# core_io1.net
KiCad netlist of a schematic drawn in EAGLE
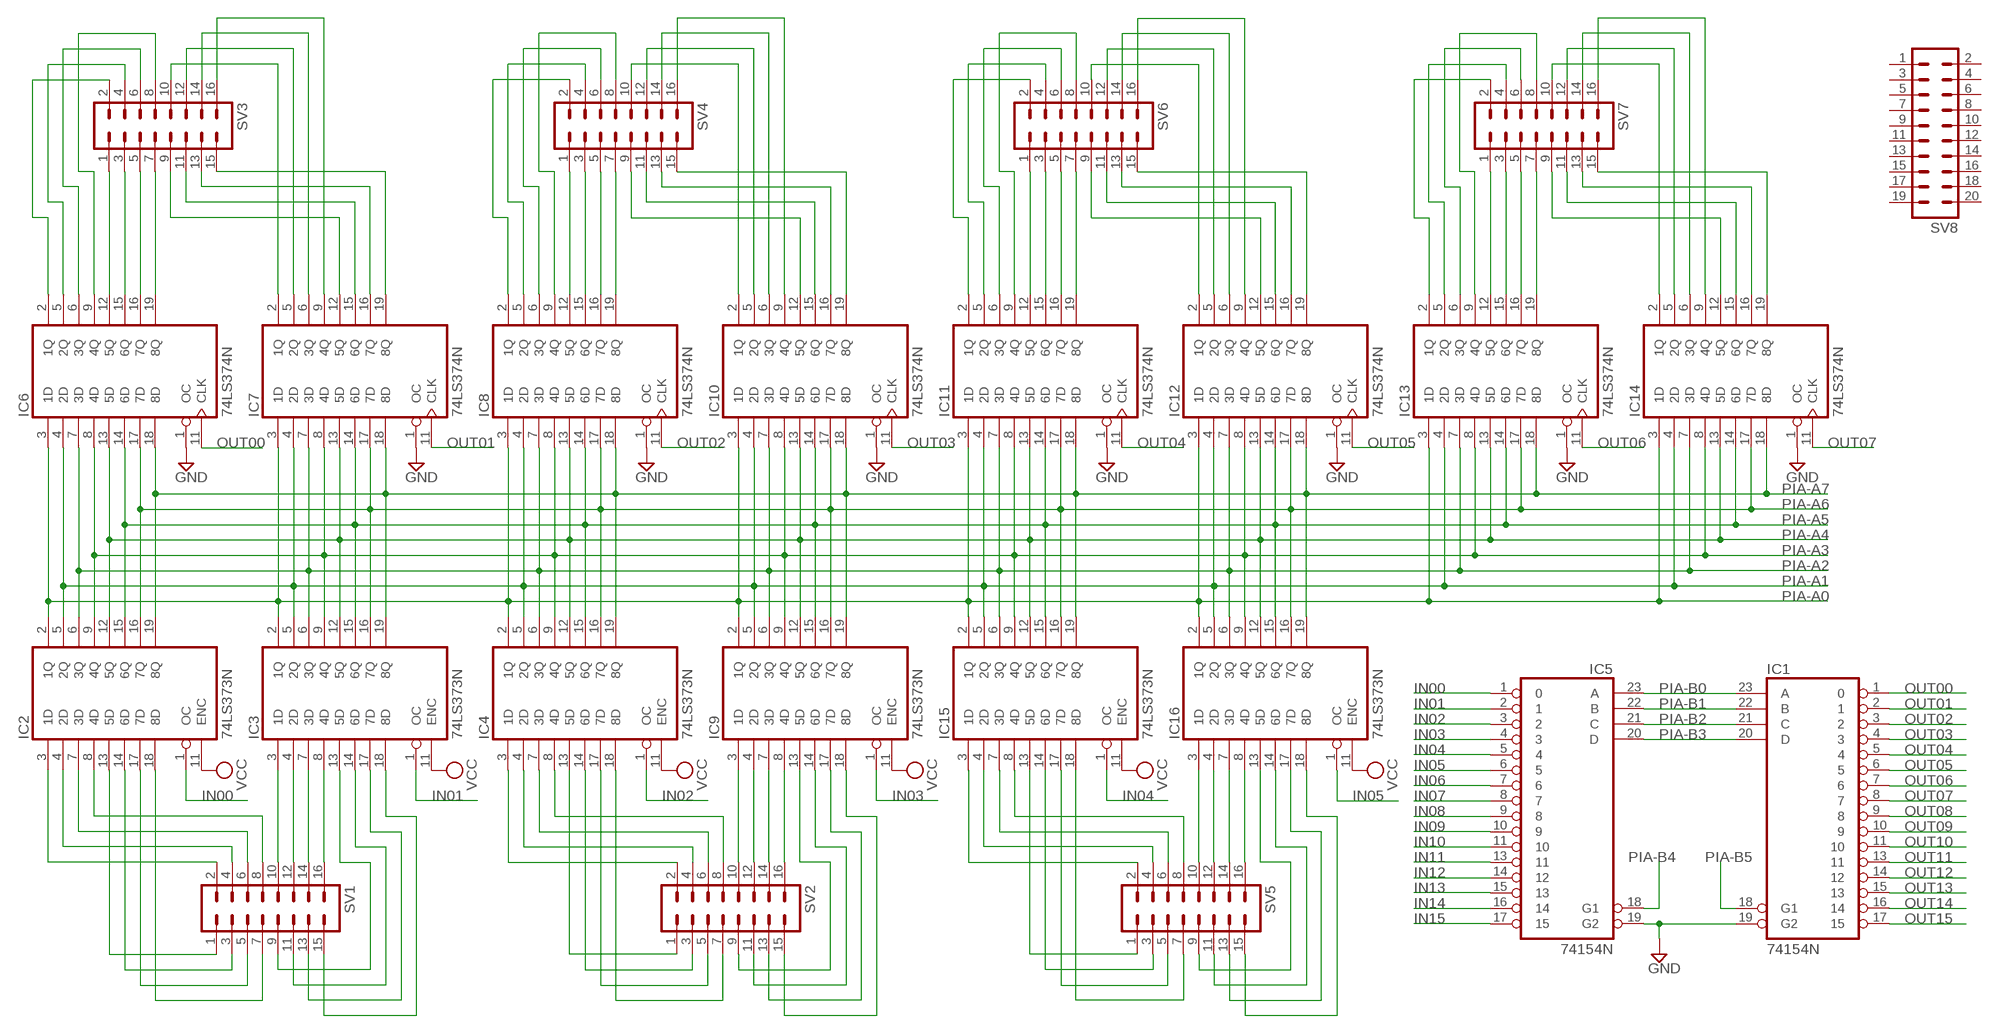
[diagram p0: schematic, sheet 1]
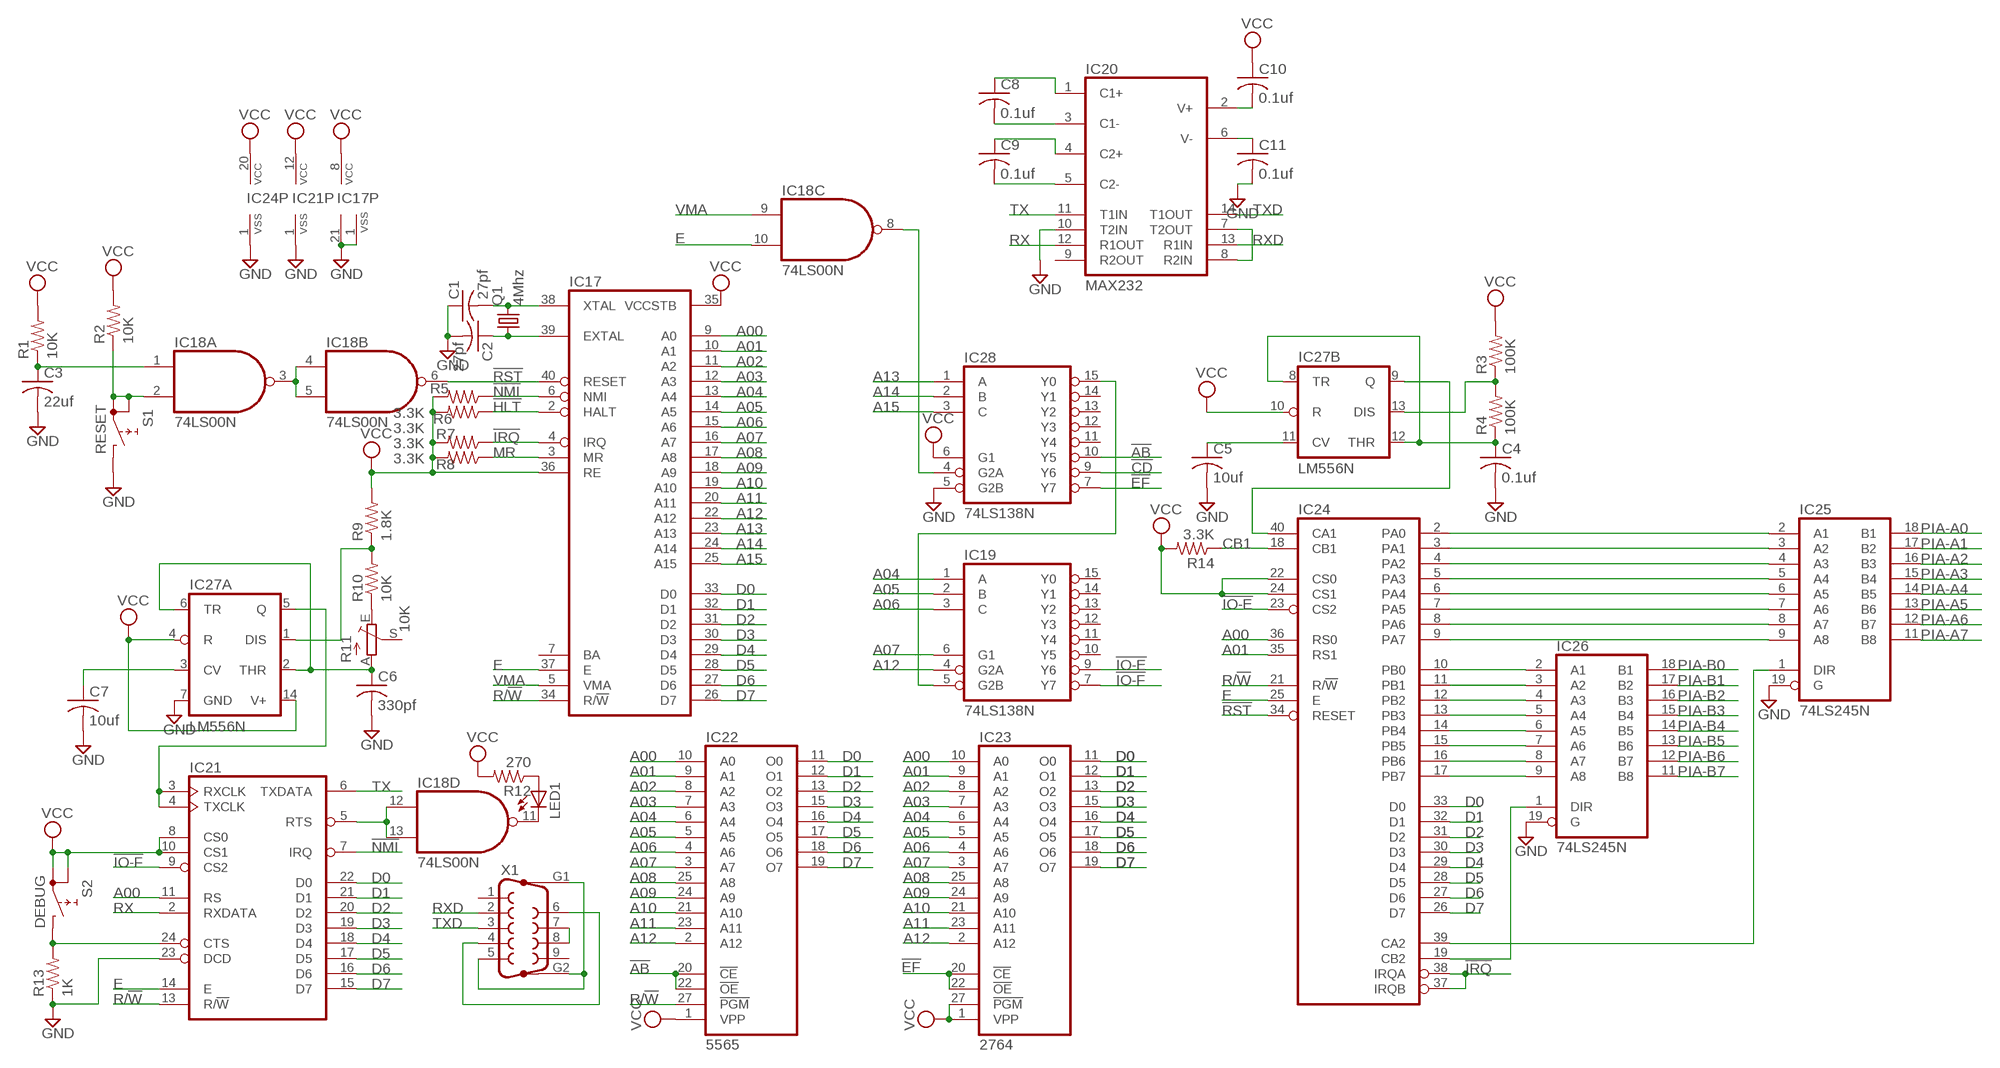
[diagram p1: schematic, sheet 2]

(export (version "E")
  (design (tool "Eeschema 10.0.6"))
  (components
    (comp (ref "C1")
      (value "27pf")
      (footprint "eagle-import:C050-025X075")
      (libsource (lib "eagle-import") (part "C-US050-025X075"))
    )
    (comp (ref "C2")
      (value "27pf")
      (footprint "eagle-import:C050-025X075")
      (libsource (lib "eagle-import") (part "C-US050-025X075"))
    )
    (comp (ref "C3")
      (value "22uf")
      (footprint "eagle-import:C050-025X075")
      (libsource (lib "eagle-import") (part "C-US050-025X075"))
    )
    (comp (ref "C4")
      (value "0.1uf")
      (footprint "eagle-import:C050-025X075")
      (libsource (lib "eagle-import") (part "C-US050-025X075"))
    )
    (comp (ref "C5")
      (value "10uf")
      (footprint "eagle-import:C050-025X075")
      (libsource (lib "eagle-import") (part "C-US050-025X075"))
    )
    (comp (ref "C6")
      (value "330pf")
      (footprint "eagle-import:C050-025X075")
      (libsource (lib "eagle-import") (part "C-US050-025X075"))
    )
    (comp (ref "C7")
      (value "10uf")
      (footprint "eagle-import:C050-025X075")
      (libsource (lib "eagle-import") (part "C-US050-025X075"))
    )
    (comp (ref "C8")
      (value "0.1uf")
      (footprint "eagle-import:C050-025X075")
      (libsource (lib "eagle-import") (part "C-US050-025X075"))
    )
    (comp (ref "C9")
      (value "0.1uf")
      (footprint "eagle-import:C050-025X075")
      (libsource (lib "eagle-import") (part "C-US050-025X075"))
    )
    (comp (ref "C10")
      (value "0.1uf")
      (footprint "eagle-import:C050-025X075")
      (libsource (lib "eagle-import") (part "C-US050-025X075"))
    )
    (comp (ref "C11")
      (value "0.1uf")
      (footprint "eagle-import:C050-025X075")
      (libsource (lib "eagle-import") (part "C-US050-025X075"))
    )
    (comp (ref "IC17")
      (value "6802")
      (footprint "eagle-import:DIL40")
      (libsource (lib "eagle-import") (part "6802"))
    )
    (comp (ref "IC18")
      (value "74LS00N")
      (footprint "eagle-import:DIL14")
      (libsource (lib "eagle-import") (part "7400NLS"))
    )
    (comp (ref "IC19")
      (value "74LS138N")
      (footprint "eagle-import:DIL16")
      (libsource (lib "eagle-import") (part "74138NLS"))
    )
    (comp (ref "IC20")
      (value "MAX232")
      (footprint "eagle-import:DIL16")
      (fields (field (name "MF") "MAXIM") (field (name "MPN") "MAX232ACPE+"))
      (libsource (lib "eagle-import") (part "MAX232"))
    )
    (comp (ref "IC21")
      (value "6850")
      (footprint "eagle-import:DIL24")
      (fields (field (name "MF") "NTE ELECTRONICS") (field (name "MPN") "NTE6850"))
      (libsource (lib "eagle-import") (part "6850"))
    )
    (comp (ref "IC22")
      (value "5565")
      (footprint "eagle-import:DIL28")
      (libsource (lib "eagle-import") (part "2764"))
    )
    (comp (ref "IC23")
      (value "2764")
      (footprint "eagle-import:DIL28")
      (libsource (lib "eagle-import") (part "2764"))
    )
    (comp (ref "IC24")
      (value "6821")
      (footprint "eagle-import:DIL40")
      (fields (field (name "MF") "NTE ELECTRONICS") (field (name "MPN") "NTE6821"))
      (libsource (lib "eagle-import") (part "6821"))
    )
    (comp (ref "IC25")
      (value "74LS245N")
      (footprint "eagle-import:DIL20")
      (libsource (lib "eagle-import") (part "74245NLS"))
    )
    (comp (ref "IC26")
      (value "74LS245N")
      (footprint "eagle-import:DIL20")
      (libsource (lib "eagle-import") (part "74245NLS"))
    )
    (comp (ref "IC27")
      (value "LM556N")
      (footprint "eagle-import:DIL14")
      (libsource (lib "eagle-import") (part "556NLM"))
    )
    (comp (ref "IC28")
      (value "74LS138N")
      (footprint "eagle-import:DIL16")
      (libsource (lib "eagle-import") (part "74138NLS"))
    )
    (comp (ref "LED1")
      (value "LED3MM")
      (footprint "eagle-import:LED3MM")
      (libsource (lib "eagle-import") (part "LED3MM"))
    )
    (comp (ref "Q1")
      (value "4Mhz")
      (footprint "eagle-import:HC18U-V")
      (libsource (lib "eagle-import") (part "CRYSTALHC18U-V"))
    )
    (comp (ref "R1")
      (value "10K")
      (footprint "eagle-import:0207_7")
      (libsource (lib "eagle-import") (part "R-US_0207/7"))
    )
    (comp (ref "R2")
      (value "10K")
      (footprint "eagle-import:0207_7")
      (libsource (lib "eagle-import") (part "R-US_0207/7"))
    )
    (comp (ref "R3")
      (value "100K")
      (footprint "eagle-import:0207_7")
      (libsource (lib "eagle-import") (part "R-US_0207/7"))
    )
    (comp (ref "R4")
      (value "100K")
      (footprint "eagle-import:0207_7")
      (libsource (lib "eagle-import") (part "R-US_0207/7"))
    )
    (comp (ref "R5")
      (value "3.3K")
      (footprint "eagle-import:0207_7")
      (libsource (lib "eagle-import") (part "R-US_0207/7"))
    )
    (comp (ref "R6")
      (value "3.3K")
      (footprint "eagle-import:0207_7")
      (libsource (lib "eagle-import") (part "R-US_0207/7"))
    )
    (comp (ref "R7")
      (value "3.3K")
      (footprint "eagle-import:0207_7")
      (libsource (lib "eagle-import") (part "R-US_0207/7"))
    )
    (comp (ref "R8")
      (value "3.3K")
      (footprint "eagle-import:0207_7")
      (libsource (lib "eagle-import") (part "R-US_0207/7"))
    )
    (comp (ref "R9")
      (value "1.8K")
      (footprint "eagle-import:0207_7")
      (libsource (lib "eagle-import") (part "R-US_0207/7"))
    )
    (comp (ref "R10")
      (value "10K")
      (footprint "eagle-import:0207_7")
      (libsource (lib "eagle-import") (part "R-US_0207/7"))
    )
    (comp (ref "R11")
      (value "10K")
      (footprint "eagle-import:SP19L")
      (libsource (lib "eagle-import") (part "TRIM_EU-B90P"))
    )
    (comp (ref "R12")
      (value "270")
      (footprint "eagle-import:0207_7")
      (libsource (lib "eagle-import") (part "R-US_0207/7"))
    )
    (comp (ref "R13")
      (value "1K")
      (footprint "eagle-import:0207_7")
      (libsource (lib "eagle-import") (part "R-US_0207/7"))
    )
    (comp (ref "R14")
      (value "3.3K")
      (footprint "eagle-import:0207_7")
      (libsource (lib "eagle-import") (part "R-US_0207/7"))
    )
    (comp (ref "S1")
      (value "RESET")
      (footprint "eagle-import:RDT1034")
      (libsource (lib "eagle-import") (part "RDT1034"))
    )
    (comp (ref "S2")
      (value "DEBUG")
      (footprint "eagle-import:RDT1034")
      (libsource (lib "eagle-import") (part "RDT1034"))
    )
    (comp (ref "X1")
      (value "F09HP")
      (footprint "eagle-import:F09HP")
      (libsource (lib "eagle-import") (part "F09HP"))
    )
    (comp (ref "IC1")
      (value "74154N")
      (footprint "eagle-import:DIL24-6")
      (libsource (lib "eagle-import") (part "74154N"))
    )
    (comp (ref "IC2")
      (value "74LS373N")
      (footprint "eagle-import:DIL20")
      (libsource (lib "eagle-import") (part "74373NLS"))
    )
    (comp (ref "IC3")
      (value "74LS373N")
      (footprint "eagle-import:DIL20")
      (libsource (lib "eagle-import") (part "74373NLS"))
    )
    (comp (ref "IC4")
      (value "74LS373N")
      (footprint "eagle-import:DIL20")
      (libsource (lib "eagle-import") (part "74373NLS"))
    )
    (comp (ref "IC5")
      (value "74154N")
      (footprint "eagle-import:DIL24-6")
      (libsource (lib "eagle-import") (part "74154N"))
    )
    (comp (ref "IC6")
      (value "74LS374N")
      (footprint "eagle-import:DIL20")
      (libsource (lib "eagle-import") (part "74374NLS"))
    )
    (comp (ref "IC7")
      (value "74LS374N")
      (footprint "eagle-import:DIL20")
      (libsource (lib "eagle-import") (part "74374NLS"))
    )
    (comp (ref "IC8")
      (value "74LS374N")
      (footprint "eagle-import:DIL20")
      (libsource (lib "eagle-import") (part "74374NLS"))
    )
    (comp (ref "IC9")
      (value "74LS373N")
      (footprint "eagle-import:DIL20")
      (libsource (lib "eagle-import") (part "74373NLS"))
    )
    (comp (ref "IC10")
      (value "74LS374N")
      (footprint "eagle-import:DIL20")
      (libsource (lib "eagle-import") (part "74374NLS"))
    )
    (comp (ref "IC11")
      (value "74LS374N")
      (footprint "eagle-import:DIL20")
      (libsource (lib "eagle-import") (part "74374NLS"))
    )
    (comp (ref "IC12")
      (value "74LS374N")
      (footprint "eagle-import:DIL20")
      (libsource (lib "eagle-import") (part "74374NLS"))
    )
    (comp (ref "IC13")
      (value "74LS374N")
      (footprint "eagle-import:DIL20")
      (libsource (lib "eagle-import") (part "74374NLS"))
    )
    (comp (ref "IC14")
      (value "74LS374N")
      (footprint "eagle-import:DIL20")
      (libsource (lib "eagle-import") (part "74374NLS"))
    )
    (comp (ref "IC15")
      (value "74LS373N")
      (footprint "eagle-import:DIL20")
      (libsource (lib "eagle-import") (part "74373NLS"))
    )
    (comp (ref "IC16")
      (value "74LS373N")
      (footprint "eagle-import:DIL20")
      (libsource (lib "eagle-import") (part "74373NLS"))
    )
    (comp (ref "SV1")
      (value "MA08-2")
      (footprint "eagle-import:MA08-2")
      (libsource (lib "eagle-import") (part "MA08-2"))
    )
    (comp (ref "SV2")
      (value "MA08-2")
      (footprint "eagle-import:MA08-2")
      (libsource (lib "eagle-import") (part "MA08-2"))
    )
    (comp (ref "SV3")
      (value "MA08-2")
      (footprint "eagle-import:MA08-2")
      (libsource (lib "eagle-import") (part "MA08-2"))
    )
    (comp (ref "SV4")
      (value "MA08-2")
      (footprint "eagle-import:MA08-2")
      (libsource (lib "eagle-import") (part "MA08-2"))
    )
    (comp (ref "SV5")
      (value "MA08-2")
      (footprint "eagle-import:MA08-2")
      (libsource (lib "eagle-import") (part "MA08-2"))
    )
    (comp (ref "SV6")
      (value "MA08-2")
      (footprint "eagle-import:MA08-2")
      (libsource (lib "eagle-import") (part "MA08-2"))
    )
    (comp (ref "SV7")
      (value "MA08-2")
      (footprint "eagle-import:MA08-2")
      (libsource (lib "eagle-import") (part "MA08-2"))
    )
    (comp (ref "SV8")
      (value "MA10-2W")
      (footprint "eagle-import:MA10-2W")
      (libsource (lib "eagle-import") (part "MA10-2W"))
    )
  )
  (nets
    (net (code "1") (name "A00") (class "Default")
      (node (ref "IC17") (pin "9") (pinfunction "A0_9") (pintype "output"))
      (node (ref "IC21") (pin "11") (pinfunction "RS_11") (pintype "input"))
      (node (ref "IC22") (pin "10") (pinfunction "A0_10") (pintype "input"))
      (node (ref "IC23") (pin "10") (pinfunction "A0_10") (pintype "input"))
      (node (ref "IC24") (pin "36") (pinfunction "RS0_36") (pintype "input"))
    )
    (net (code "2") (name "A01") (class "Default")
      (node (ref "IC17") (pin "10") (pinfunction "A1_10") (pintype "output"))
      (node (ref "IC22") (pin "9") (pinfunction "A1_9") (pintype "input"))
      (node (ref "IC23") (pin "9") (pinfunction "A1_9") (pintype "input"))
      (node (ref "IC24") (pin "35") (pinfunction "RS1_35") (pintype "input"))
    )
    (net (code "3") (name "A02") (class "Default")
      (node (ref "IC17") (pin "11") (pinfunction "A2_11") (pintype "output"))
      (node (ref "IC22") (pin "8") (pinfunction "A2_8") (pintype "input"))
      (node (ref "IC23") (pin "8") (pinfunction "A2_8") (pintype "input"))
    )
    (net (code "4") (name "A03") (class "Default")
      (node (ref "IC17") (pin "12") (pinfunction "A3_12") (pintype "output"))
      (node (ref "IC22") (pin "7") (pinfunction "A3_7") (pintype "input"))
      (node (ref "IC23") (pin "7") (pinfunction "A3_7") (pintype "input"))
    )
    (net (code "5") (name "A04") (class "Default")
      (node (ref "IC17") (pin "13") (pinfunction "A4_13") (pintype "output"))
      (node (ref "IC19") (pin "1") (pinfunction "A_1") (pintype "input"))
      (node (ref "IC22") (pin "6") (pinfunction "A4_6") (pintype "input"))
      (node (ref "IC23") (pin "6") (pinfunction "A4_6") (pintype "input"))
    )
    (net (code "6") (name "A05") (class "Default")
      (node (ref "IC17") (pin "14") (pinfunction "A5_14") (pintype "output"))
      (node (ref "IC19") (pin "2") (pinfunction "B_2") (pintype "input"))
      (node (ref "IC22") (pin "5") (pinfunction "A5_5") (pintype "input"))
      (node (ref "IC23") (pin "5") (pinfunction "A5_5") (pintype "input"))
    )
    (net (code "7") (name "A06") (class "Default")
      (node (ref "IC17") (pin "15") (pinfunction "A6_15") (pintype "output"))
      (node (ref "IC19") (pin "3") (pinfunction "C_3") (pintype "input"))
      (node (ref "IC22") (pin "4") (pinfunction "A6_4") (pintype "input"))
      (node (ref "IC23") (pin "4") (pinfunction "A6_4") (pintype "input"))
    )
    (net (code "8") (name "A07") (class "Default")
      (node (ref "IC17") (pin "16") (pinfunction "A7_16") (pintype "output"))
      (node (ref "IC19") (pin "6") (pinfunction "G1_6") (pintype "input"))
      (node (ref "IC22") (pin "3") (pinfunction "A7_3") (pintype "input"))
      (node (ref "IC23") (pin "3") (pinfunction "A7_3") (pintype "input"))
    )
    (net (code "9") (name "A08") (class "Default")
      (node (ref "IC17") (pin "17") (pinfunction "A8_17") (pintype "output"))
      (node (ref "IC22") (pin "25") (pinfunction "A8_25") (pintype "input"))
      (node (ref "IC23") (pin "25") (pinfunction "A8_25") (pintype "input"))
    )
    (net (code "10") (name "A09") (class "Default")
      (node (ref "IC17") (pin "18") (pinfunction "A9_18") (pintype "output"))
      (node (ref "IC22") (pin "24") (pinfunction "A9_24") (pintype "input"))
      (node (ref "IC23") (pin "24") (pinfunction "A9_24") (pintype "input"))
    )
    (net (code "11") (name "A10") (class "Default")
      (node (ref "IC17") (pin "19") (pinfunction "A10_19") (pintype "output"))
      (node (ref "IC22") (pin "21") (pinfunction "A10_21") (pintype "input"))
      (node (ref "IC23") (pin "21") (pinfunction "A10_21") (pintype "input"))
    )
    (net (code "12") (name "A11") (class "Default")
      (node (ref "IC17") (pin "20") (pinfunction "A11_20") (pintype "output"))
      (node (ref "IC22") (pin "23") (pinfunction "A11_23") (pintype "input"))
      (node (ref "IC23") (pin "23") (pinfunction "A11_23") (pintype "input"))
    )
    (net (code "13") (name "A12") (class "Default")
      (node (ref "IC17") (pin "22") (pinfunction "A12_22") (pintype "output"))
      (node (ref "IC19") (pin "4") (pinfunction "G2A_4") (pintype "input"))
      (node (ref "IC22") (pin "2") (pinfunction "A12_2") (pintype "input"))
      (node (ref "IC23") (pin "2") (pinfunction "A12_2") (pintype "input"))
    )
    (net (code "14") (name "A13") (class "Default")
      (node (ref "IC17") (pin "23") (pinfunction "A13_23") (pintype "output"))
      (node (ref "IC28") (pin "1") (pinfunction "A_1") (pintype "input"))
    )
    (net (code "15") (name "A14") (class "Default")
      (node (ref "IC17") (pin "24") (pinfunction "A14_24") (pintype "output"))
      (node (ref "IC28") (pin "2") (pinfunction "B_2") (pintype "input"))
    )
    (net (code "16") (name "A15") (class "Default")
      (node (ref "IC17") (pin "25") (pinfunction "A15_25") (pintype "output"))
      (node (ref "IC28") (pin "3") (pinfunction "C_3") (pintype "input"))
    )
    (net (code "17") (name "CB1") (class "Default")
      (node (ref "IC24") (pin "18") (pinfunction "CB1_18") (pintype "input"))
      (node (ref "R14") (pin "1") (pinfunction "1_1") (pintype "passive"))
    )
    (net (code "18") (name "D0") (class "Default")
      (node (ref "IC17") (pin "33") (pinfunction "D0_33") (pintype "bidirectional"))
      (node (ref "IC21") (pin "22") (pinfunction "D0_22") (pintype "bidirectional"))
      (node (ref "IC22") (pin "11") (pinfunction "O0_11") (pintype "tri_state"))
      (node (ref "IC23") (pin "11") (pinfunction "O0_11") (pintype "tri_state"))
      (node (ref "IC24") (pin "33") (pinfunction "D0_33") (pintype "bidirectional"))
    )
    (net (code "19") (name "D1") (class "Default")
      (node (ref "IC17") (pin "32") (pinfunction "D1_32") (pintype "bidirectional"))
      (node (ref "IC21") (pin "21") (pinfunction "D1_21") (pintype "bidirectional"))
      (node (ref "IC22") (pin "12") (pinfunction "O1_12") (pintype "tri_state"))
      (node (ref "IC23") (pin "12") (pinfunction "O1_12") (pintype "tri_state"))
      (node (ref "IC24") (pin "32") (pinfunction "D1_32") (pintype "bidirectional"))
    )
    (net (code "20") (name "D2") (class "Default")
      (node (ref "IC17") (pin "31") (pinfunction "D2_31") (pintype "bidirectional"))
      (node (ref "IC21") (pin "20") (pinfunction "D2_20") (pintype "bidirectional"))
      (node (ref "IC22") (pin "13") (pinfunction "O2_13") (pintype "tri_state"))
      (node (ref "IC23") (pin "13") (pinfunction "O2_13") (pintype "tri_state"))
      (node (ref "IC24") (pin "31") (pinfunction "D2_31") (pintype "bidirectional"))
    )
    (net (code "21") (name "D3") (class "Default")
      (node (ref "IC17") (pin "30") (pinfunction "D3_30") (pintype "bidirectional"))
      (node (ref "IC21") (pin "19") (pinfunction "D3_19") (pintype "bidirectional"))
      (node (ref "IC22") (pin "15") (pinfunction "O3_15") (pintype "tri_state"))
      (node (ref "IC23") (pin "15") (pinfunction "O3_15") (pintype "tri_state"))
      (node (ref "IC24") (pin "30") (pinfunction "D3_30") (pintype "bidirectional"))
    )
    (net (code "22") (name "D4") (class "Default")
      (node (ref "IC17") (pin "29") (pinfunction "D4_29") (pintype "bidirectional"))
      (node (ref "IC21") (pin "18") (pinfunction "D4_18") (pintype "bidirectional"))
      (node (ref "IC22") (pin "16") (pinfunction "O4_16") (pintype "tri_state"))
      (node (ref "IC23") (pin "16") (pinfunction "O4_16") (pintype "tri_state"))
      (node (ref "IC24") (pin "29") (pinfunction "D4_29") (pintype "bidirectional"))
    )
    (net (code "23") (name "D5") (class "Default")
      (node (ref "IC17") (pin "28") (pinfunction "D5_28") (pintype "bidirectional"))
      (node (ref "IC21") (pin "17") (pinfunction "D5_17") (pintype "bidirectional"))
      (node (ref "IC22") (pin "17") (pinfunction "O5_17") (pintype "tri_state"))
      (node (ref "IC23") (pin "17") (pinfunction "O5_17") (pintype "tri_state"))
      (node (ref "IC24") (pin "28") (pinfunction "D5_28") (pintype "bidirectional"))
    )
    (net (code "24") (name "D6") (class "Default")
      (node (ref "IC17") (pin "27") (pinfunction "D6_27") (pintype "bidirectional"))
      (node (ref "IC21") (pin "16") (pinfunction "D6_16") (pintype "bidirectional"))
      (node (ref "IC22") (pin "18") (pinfunction "O6_18") (pintype "tri_state"))
      (node (ref "IC23") (pin "18") (pinfunction "O6_18") (pintype "tri_state"))
      (node (ref "IC24") (pin "27") (pinfunction "D6_27") (pintype "bidirectional"))
    )
    (net (code "25") (name "D7") (class "Default")
      (node (ref "IC17") (pin "26") (pinfunction "D7_26") (pintype "bidirectional"))
      (node (ref "IC21") (pin "15") (pinfunction "D7_15") (pintype "bidirectional"))
      (node (ref "IC22") (pin "19") (pinfunction "O7_19") (pintype "tri_state"))
      (node (ref "IC23") (pin "19") (pinfunction "O7_19") (pintype "tri_state"))
      (node (ref "IC24") (pin "26") (pinfunction "D7_26") (pintype "bidirectional"))
    )
    (net (code "26") (name "E") (class "Default")
      (node (ref "IC17") (pin "37") (pinfunction "E_37") (pintype "output"))
      (node (ref "IC18") (pin "10") (pinfunction "I1_10") (pintype "input"))
      (node (ref "IC21") (pin "14") (pinfunction "E_14") (pintype "input"))
      (node (ref "IC24") (pin "25") (pinfunction "E_25") (pintype "input"))
    )
    (net (code "27") (name "GND") (class "Default")
      (node (ref "C1") (pin "1") (pinfunction "1_1") (pintype "passive"))
      (node (ref "C11") (pin "2") (pinfunction "2_2") (pintype "passive"))
      (node (ref "C2") (pin "2") (pinfunction "2_2") (pintype "passive"))
      (node (ref "C3") (pin "2") (pinfunction "2_2") (pintype "passive"))
      (node (ref "C4") (pin "2") (pinfunction "2_2") (pintype "passive"))
      (node (ref "C5") (pin "2") (pinfunction "2_2") (pintype "passive"))
      (node (ref "C6") (pin "2") (pinfunction "2_2") (pintype "passive"))
      (node (ref "C7") (pin "2") (pinfunction "2_2") (pintype "passive"))
      (node (ref "IC1") (pin "19") (pinfunction "G2_19") (pintype "input"))
      (node (ref "IC10") (pin "1") (pinfunction "OC_1") (pintype "input"))
      (node (ref "IC11") (pin "1") (pinfunction "OC_1") (pintype "input"))
      (node (ref "IC12") (pin "1") (pinfunction "OC_1") (pintype "input"))
      (node (ref "IC13") (pin "1") (pinfunction "OC_1") (pintype "input"))
      (node (ref "IC14") (pin "1") (pinfunction "OC_1") (pintype "input"))
      (node (ref "IC17") (pin "1") (pinfunction "VSS_1") (pintype "power_in"))
      (node (ref "IC17") (pin "21") (pinfunction "VSS_21") (pintype "power_in"))
      (node (ref "IC20") (pin "10") (pinfunction "T2IN_10") (pintype "input"))
      (node (ref "IC21") (pin "1") (pinfunction "VSS_1") (pintype "power_in"))
      (node (ref "IC21") (pin "23") (pinfunction "DCD_23") (pintype "input"))
      (node (ref "IC24") (pin "1") (pinfunction "VSS_1") (pintype "power_in"))
      (node (ref "IC25") (pin "19") (pinfunction "G_19") (pintype "input"))
      (node (ref "IC26") (pin "19") (pinfunction "G_19") (pintype "input"))
      (node (ref "IC27") (pin "7") (pinfunction "GND_7") (pintype "power_in"))
      (node (ref "IC28") (pin "5") (pinfunction "G2B_5") (pintype "input"))
      (node (ref "IC5") (pin "19") (pinfunction "G2_19") (pintype "input"))
      (node (ref "IC6") (pin "1") (pinfunction "OC_1") (pintype "input"))
      (node (ref "IC7") (pin "1") (pinfunction "OC_1") (pintype "input"))
      (node (ref "IC8") (pin "1") (pinfunction "OC_1") (pintype "input"))
      (node (ref "R13") (pin "1") (pinfunction "1_1") (pintype "passive"))
      (node (ref "S1") (pin "B") (pinfunction "B_B") (pintype "passive"))
    )
    (net (code "28") (name "IN00") (class "Default")
      (node (ref "IC2") (pin "1") (pinfunction "OC_1") (pintype "input"))
      (node (ref "IC5") (pin "1") (pinfunction "0_1") (pintype "output"))
    )
    (net (code "29") (name "IN01") (class "Default")
      (node (ref "IC3") (pin "1") (pinfunction "OC_1") (pintype "input"))
      (node (ref "IC5") (pin "2") (pinfunction "1_2") (pintype "output"))
    )
    (net (code "30") (name "IN02") (class "Default")
      (node (ref "IC4") (pin "1") (pinfunction "OC_1") (pintype "input"))
      (node (ref "IC5") (pin "3") (pinfunction "2_3") (pintype "output"))
    )
    (net (code "31") (name "IN03") (class "Default")
      (node (ref "IC5") (pin "4") (pinfunction "3_4") (pintype "output"))
      (node (ref "IC9") (pin "1") (pinfunction "OC_1") (pintype "input"))
    )
    (net (code "32") (name "IN04") (class "Default")
      (node (ref "IC15") (pin "1") (pinfunction "OC_1") (pintype "input"))
      (node (ref "IC5") (pin "5") (pinfunction "4_5") (pintype "output"))
    )
    (net (code "33") (name "IN05") (class "Default")
      (node (ref "IC16") (pin "1") (pinfunction "OC_1") (pintype "input"))
      (node (ref "IC5") (pin "6") (pinfunction "5_6") (pintype "output"))
    )
    (net (code "34") (name "IN06") (class "Default")
      (node (ref "IC5") (pin "7") (pinfunction "6_7") (pintype "output"))
    )
    (net (code "35") (name "IN07") (class "Default")
      (node (ref "IC5") (pin "8") (pinfunction "7_8") (pintype "output"))
    )
    (net (code "36") (name "IN08") (class "Default")
      (node (ref "IC5") (pin "9") (pinfunction "8_9") (pintype "output"))
    )
    (net (code "37") (name "IN09") (class "Default")
      (node (ref "IC5") (pin "10") (pinfunction "9_10") (pintype "output"))
    )
    (net (code "38") (name "IN10") (class "Default")
      (node (ref "IC5") (pin "11") (pinfunction "10_11") (pintype "output"))
    )
    (net (code "39") (name "IN11") (class "Default")
      (node (ref "IC5") (pin "13") (pinfunction "11_13") (pintype "output"))
    )
    (net (code "40") (name "IN12") (class "Default")
      (node (ref "IC5") (pin "14") (pinfunction "12_14") (pintype "output"))
    )
    (net (code "41") (name "IN13") (class "Default")
      (node (ref "IC5") (pin "15") (pinfunction "13_15") (pintype "output"))
    )
    (net (code "42") (name "IN14") (class "Default")
      (node (ref "IC5") (pin "16") (pinfunction "14_16") (pintype "output"))
    )
    (net (code "43") (name "IN15") (class "Default")
      (node (ref "IC5") (pin "17") (pinfunction "15_17") (pintype "output"))
    )
    (net (code "44") (name "MR") (class "Default")
      (node (ref "IC17") (pin "3") (pinfunction "MR_3") (pintype "input"))
      (node (ref "R8") (pin "1") (pinfunction "1_1") (pintype "passive"))
    )
    (net (code "45") (name "Net-(IC2A-1D)") (class "Default")
      (node (ref "IC2") (pin "3") (pinfunction "1D_3") (pintype "input"))
      (node (ref "SV1") (pin "2") (pinfunction "2_2") (pintype "passive"))
    )
    (net (code "46") (name "Net-(IC2A-2D)") (class "Default")
      (node (ref "IC2") (pin "4") (pinfunction "2D_4") (pintype "input"))
      (node (ref "SV1") (pin "4") (pinfunction "4_4") (pintype "passive"))
    )
    (net (code "47") (name "Net-(IC2A-3D)") (class "Default")
      (node (ref "IC2") (pin "7") (pinfunction "3D_7") (pintype "input"))
      (node (ref "SV1") (pin "6") (pinfunction "6_6") (pintype "passive"))
    )
    (net (code "48") (name "Net-(IC2A-4D)") (class "Default")
      (node (ref "IC2") (pin "8") (pinfunction "4D_8") (pintype "input"))
      (node (ref "SV1") (pin "8") (pinfunction "8_8") (pintype "passive"))
    )
    (net (code "49") (name "Net-(IC2A-5D)") (class "Default")
      (node (ref "IC2") (pin "13") (pinfunction "5D_13") (pintype "input"))
      (node (ref "SV1") (pin "1") (pinfunction "1_1") (pintype "passive"))
    )
    (net (code "50") (name "Net-(IC2A-6D)") (class "Default")
      (node (ref "IC2") (pin "14") (pinfunction "6D_14") (pintype "input"))
      (node (ref "SV1") (pin "3") (pinfunction "3_3") (pintype "passive"))
    )
    (net (code "51") (name "Net-(IC2A-7D)") (class "Default")
      (node (ref "IC2") (pin "17") (pinfunction "7D_17") (pintype "input"))
      (node (ref "SV1") (pin "5") (pinfunction "5_5") (pintype "passive"))
    )
    (net (code "52") (name "Net-(IC2A-8D)") (class "Default")
      (node (ref "IC2") (pin "18") (pinfunction "8D_18") (pintype "input"))
      (node (ref "SV1") (pin "7") (pinfunction "7_7") (pintype "passive"))
    )
    (net (code "53") (name "Net-(IC3A-1D)") (class "Default")
      (node (ref "IC3") (pin "3") (pinfunction "1D_3") (pintype "input"))
      (node (ref "SV1") (pin "10") (pinfunction "10_10") (pintype "passive"))
    )
    (net (code "54") (name "Net-(IC3A-2D)") (class "Default")
      (node (ref "IC3") (pin "4") (pinfunction "2D_4") (pintype "input"))
      (node (ref "SV1") (pin "12") (pinfunction "12_12") (pintype "passive"))
    )
    (net (code "55") (name "Net-(IC3A-3D)") (class "Default")
      (node (ref "IC3") (pin "7") (pinfunction "3D_7") (pintype "input"))
      (node (ref "SV1") (pin "14") (pinfunction "14_14") (pintype "passive"))
    )
    (net (code "56") (name "Net-(IC3A-4D)") (class "Default")
      (node (ref "IC3") (pin "8") (pinfunction "4D_8") (pintype "input"))
      (node (ref "SV1") (pin "16") (pinfunction "16_16") (pintype "passive"))
    )
    (net (code "57") (name "Net-(IC3A-5D)") (class "Default")
      (node (ref "IC3") (pin "13") (pinfunction "5D_13") (pintype "input"))
      (node (ref "SV1") (pin "9") (pinfunction "9_9") (pintype "passive"))
    )
    (net (code "58") (name "Net-(IC3A-6D)") (class "Default")
      (node (ref "IC3") (pin "14") (pinfunction "6D_14") (pintype "input"))
      (node (ref "SV1") (pin "11") (pinfunction "11_11") (pintype "passive"))
    )
    (net (code "59") (name "Net-(IC3A-7D)") (class "Default")
      (node (ref "IC3") (pin "17") (pinfunction "7D_17") (pintype "input"))
      (node (ref "SV1") (pin "13") (pinfunction "13_13") (pintype "passive"))
    )
    (net (code "60") (name "Net-(IC3A-8D)") (class "Default")
      (node (ref "IC3") (pin "18") (pinfunction "8D_18") (pintype "input"))
      (node (ref "SV1") (pin "15") (pinfunction "15_15") (pintype "passive"))
    )
    (net (code "61") (name "Net-(IC4A-1D)") (class "Default")
      (node (ref "IC4") (pin "3") (pinfunction "1D_3") (pintype "input"))
      (node (ref "SV2") (pin "2") (pinfunction "2_2") (pintype "passive"))
    )
    (net (code "62") (name "Net-(IC4A-2D)") (class "Default")
      (node (ref "IC4") (pin "4") (pinfunction "2D_4") (pintype "input"))
      (node (ref "SV2") (pin "4") (pinfunction "4_4") (pintype "passive"))
    )
    (net (code "63") (name "Net-(IC4A-3D)") (class "Default")
      (node (ref "IC4") (pin "7") (pinfunction "3D_7") (pintype "input"))
      (node (ref "SV2") (pin "6") (pinfunction "6_6") (pintype "passive"))
    )
    (net (code "64") (name "Net-(IC4A-4D)") (class "Default")
      (node (ref "IC4") (pin "8") (pinfunction "4D_8") (pintype "input"))
      (node (ref "SV2") (pin "8") (pinfunction "8_8") (pintype "passive"))
    )
    (net (code "65") (name "Net-(IC4A-5D)") (class "Default")
      (node (ref "IC4") (pin "13") (pinfunction "5D_13") (pintype "input"))
      (node (ref "SV2") (pin "1") (pinfunction "1_1") (pintype "passive"))
    )
    (net (code "66") (name "Net-(IC4A-6D)") (class "Default")
      (node (ref "IC4") (pin "14") (pinfunction "6D_14") (pintype "input"))
      (node (ref "SV2") (pin "3") (pinfunction "3_3") (pintype "passive"))
    )
    (net (code "67") (name "Net-(IC4A-7D)") (class "Default")
      (node (ref "IC4") (pin "17") (pinfunction "7D_17") (pintype "input"))
      (node (ref "SV2") (pin "5") (pinfunction "5_5") (pintype "passive"))
    )
    (net (code "68") (name "Net-(IC4A-8D)") (class "Default")
      (node (ref "IC4") (pin "18") (pinfunction "8D_18") (pintype "input"))
      (node (ref "SV2") (pin "7") (pinfunction "7_7") (pintype "passive"))
    )
    (net (code "69") (name "Net-(IC6A-1Q)") (class "Default")
      (node (ref "IC6") (pin "2") (pinfunction "1Q_2") (pintype "tri_state"))
      (node (ref "SV3") (pin "2") (pinfunction "2_2") (pintype "passive"))
    )
    (net (code "70") (name "Net-(IC6A-2Q)") (class "Default")
      (node (ref "IC6") (pin "5") (pinfunction "2Q_5") (pintype "tri_state"))
      (node (ref "SV3") (pin "4") (pinfunction "4_4") (pintype "passive"))
    )
    (net (code "71") (name "Net-(IC6A-3Q)") (class "Default")
      (node (ref "IC6") (pin "6") (pinfunction "3Q_6") (pintype "tri_state"))
      (node (ref "SV3") (pin "6") (pinfunction "6_6") (pintype "passive"))
    )
    (net (code "72") (name "Net-(IC6A-4Q)") (class "Default")
      (node (ref "IC6") (pin "9") (pinfunction "4Q_9") (pintype "tri_state"))
      (node (ref "SV3") (pin "8") (pinfunction "8_8") (pintype "passive"))
    )
    (net (code "73") (name "Net-(IC6A-5Q)") (class "Default")
      (node (ref "IC6") (pin "12") (pinfunction "5Q_12") (pintype "tri_state"))
      (node (ref "SV3") (pin "1") (pinfunction "1_1") (pintype "passive"))
    )
    (net (code "74") (name "Net-(IC6A-6Q)") (class "Default")
      (node (ref "IC6") (pin "15") (pinfunction "6Q_15") (pintype "tri_state"))
      (node (ref "SV3") (pin "3") (pinfunction "3_3") (pintype "passive"))
    )
    (net (code "75") (name "Net-(IC6A-7Q)") (class "Default")
      (node (ref "IC6") (pin "16") (pinfunction "7Q_16") (pintype "tri_state"))
      (node (ref "SV3") (pin "5") (pinfunction "5_5") (pintype "passive"))
    )
    (net (code "76") (name "Net-(IC6A-8Q)") (class "Default")
      (node (ref "IC6") (pin "19") (pinfunction "8Q_19") (pintype "tri_state"))
      (node (ref "SV3") (pin "7") (pinfunction "7_7") (pintype "passive"))
    )
    (net (code "77") (name "Net-(IC7A-1Q)") (class "Default")
      (node (ref "IC7") (pin "2") (pinfunction "1Q_2") (pintype "tri_state"))
      (node (ref "SV3") (pin "10") (pinfunction "10_10") (pintype "passive"))
    )
    (net (code "78") (name "Net-(IC7A-2Q)") (class "Default")
      (node (ref "IC7") (pin "5") (pinfunction "2Q_5") (pintype "tri_state"))
      (node (ref "SV3") (pin "12") (pinfunction "12_12") (pintype "passive"))
    )
    (net (code "79") (name "Net-(IC7A-3Q)") (class "Default")
      (node (ref "IC7") (pin "6") (pinfunction "3Q_6") (pintype "tri_state"))
      (node (ref "SV3") (pin "14") (pinfunction "14_14") (pintype "passive"))
    )
    (net (code "80") (name "Net-(IC7A-4Q)") (class "Default")
      (node (ref "IC7") (pin "9") (pinfunction "4Q_9") (pintype "tri_state"))
      (node (ref "SV3") (pin "16") (pinfunction "16_16") (pintype "passive"))
    )
    (net (code "81") (name "Net-(IC7A-5Q)") (class "Default")
      (node (ref "IC7") (pin "12") (pinfunction "5Q_12") (pintype "tri_state"))
      (node (ref "SV3") (pin "9") (pinfunction "9_9") (pintype "passive"))
    )
    (net (code "82") (name "Net-(IC7A-6Q)") (class "Default")
      (node (ref "IC7") (pin "15") (pinfunction "6Q_15") (pintype "tri_state"))
      (node (ref "SV3") (pin "11") (pinfunction "11_11") (pintype "passive"))
    )
    (net (code "83") (name "Net-(IC7A-7Q)") (class "Default")
      (node (ref "IC7") (pin "16") (pinfunction "7Q_16") (pintype "tri_state"))
      (node (ref "SV3") (pin "13") (pinfunction "13_13") (pintype "passive"))
    )
    (net (code "84") (name "Net-(IC7A-8Q)") (class "Default")
      (node (ref "IC7") (pin "19") (pinfunction "8Q_19") (pintype "tri_state"))
      (node (ref "SV3") (pin "15") (pinfunction "15_15") (pintype "passive"))
    )
    (net (code "85") (name "Net-(IC8A-1Q)") (class "Default")
      (node (ref "IC8") (pin "2") (pinfunction "1Q_2") (pintype "tri_state"))
      (node (ref "SV4") (pin "2") (pinfunction "2_2") (pintype "passive"))
    )
    (net (code "86") (name "Net-(IC8A-2Q)") (class "Default")
      (node (ref "IC8") (pin "5") (pinfunction "2Q_5") (pintype "tri_state"))
      (node (ref "SV4") (pin "4") (pinfunction "4_4") (pintype "passive"))
    )
    (net (code "87") (name "Net-(IC8A-3Q)") (class "Default")
      (node (ref "IC8") (pin "6") (pinfunction "3Q_6") (pintype "tri_state"))
      (node (ref "SV4") (pin "6") (pinfunction "6_6") (pintype "passive"))
    )
    (net (code "88") (name "Net-(IC8A-4Q)") (class "Default")
      (node (ref "IC8") (pin "9") (pinfunction "4Q_9") (pintype "tri_state"))
      (node (ref "SV4") (pin "8") (pinfunction "8_8") (pintype "passive"))
    )
    (net (code "89") (name "Net-(IC8A-5Q)") (class "Default")
      (node (ref "IC8") (pin "12") (pinfunction "5Q_12") (pintype "tri_state"))
      (node (ref "SV4") (pin "1") (pinfunction "1_1") (pintype "passive"))
    )
    (net (code "90") (name "Net-(IC8A-6Q)") (class "Default")
      (node (ref "IC8") (pin "15") (pinfunction "6Q_15") (pintype "tri_state"))
      (node (ref "SV4") (pin "3") (pinfunction "3_3") (pintype "passive"))
    )
    (net (code "91") (name "Net-(IC8A-7Q)") (class "Default")
      (node (ref "IC8") (pin "16") (pinfunction "7Q_16") (pintype "tri_state"))
      (node (ref "SV4") (pin "5") (pinfunction "5_5") (pintype "passive"))
    )
    (net (code "92") (name "Net-(IC8A-8Q)") (class "Default")
      (node (ref "IC8") (pin "19") (pinfunction "8Q_19") (pintype "tri_state"))
      (node (ref "SV4") (pin "7") (pinfunction "7_7") (pintype "passive"))
    )
    (net (code "93") (name "Net-(IC9A-1D)") (class "Default")
      (node (ref "IC9") (pin "3") (pinfunction "1D_3") (pintype "input"))
      (node (ref "SV2") (pin "10") (pinfunction "10_10") (pintype "passive"))
    )
    (net (code "94") (name "Net-(IC9A-2D)") (class "Default")
      (node (ref "IC9") (pin "4") (pinfunction "2D_4") (pintype "input"))
      (node (ref "SV2") (pin "12") (pinfunction "12_12") (pintype "passive"))
    )
    (net (code "95") (name "Net-(IC9A-3D)") (class "Default")
      (node (ref "IC9") (pin "7") (pinfunction "3D_7") (pintype "input"))
      (node (ref "SV2") (pin "14") (pinfunction "14_14") (pintype "passive"))
    )
    (net (code "96") (name "Net-(IC9A-4D)") (class "Default")
      (node (ref "IC9") (pin "8") (pinfunction "4D_8") (pintype "input"))
      (node (ref "SV2") (pin "16") (pinfunction "16_16") (pintype "passive"))
    )
    (net (code "97") (name "Net-(IC9A-5D)") (class "Default")
      (node (ref "IC9") (pin "13") (pinfunction "5D_13") (pintype "input"))
      (node (ref "SV2") (pin "9") (pinfunction "9_9") (pintype "passive"))
    )
    (net (code "98") (name "Net-(IC9A-6D)") (class "Default")
      (node (ref "IC9") (pin "14") (pinfunction "6D_14") (pintype "input"))
      (node (ref "SV2") (pin "11") (pinfunction "11_11") (pintype "passive"))
    )
    (net (code "99") (name "Net-(IC9A-7D)") (class "Default")
      (node (ref "IC9") (pin "17") (pinfunction "7D_17") (pintype "input"))
      (node (ref "SV2") (pin "13") (pinfunction "13_13") (pintype "passive"))
    )
    (net (code "100") (name "Net-(IC9A-8D)") (class "Default")
      (node (ref "IC9") (pin "18") (pinfunction "8D_18") (pintype "input"))
      (node (ref "SV2") (pin "15") (pinfunction "15_15") (pintype "passive"))
    )
    (net (code "101") (name "Net-(IC10A-1Q)") (class "Default")
      (node (ref "IC10") (pin "2") (pinfunction "1Q_2") (pintype "tri_state"))
      (node (ref "SV4") (pin "10") (pinfunction "10_10") (pintype "passive"))
    )
    (net (code "102") (name "Net-(IC10A-2Q)") (class "Default")
      (node (ref "IC10") (pin "5") (pinfunction "2Q_5") (pintype "tri_state"))
      (node (ref "SV4") (pin "12") (pinfunction "12_12") (pintype "passive"))
    )
    (net (code "103") (name "Net-(IC10A-3Q)") (class "Default")
      (node (ref "IC10") (pin "6") (pinfunction "3Q_6") (pintype "tri_state"))
      (node (ref "SV4") (pin "14") (pinfunction "14_14") (pintype "passive"))
    )
    (net (code "104") (name "Net-(IC10A-4Q)") (class "Default")
      (node (ref "IC10") (pin "9") (pinfunction "4Q_9") (pintype "tri_state"))
      (node (ref "SV4") (pin "16") (pinfunction "16_16") (pintype "passive"))
    )
    (net (code "105") (name "Net-(IC10A-5Q)") (class "Default")
      (node (ref "IC10") (pin "12") (pinfunction "5Q_12") (pintype "tri_state"))
      (node (ref "SV4") (pin "9") (pinfunction "9_9") (pintype "passive"))
    )
    (net (code "106") (name "Net-(IC10A-6Q)") (class "Default")
      (node (ref "IC10") (pin "15") (pinfunction "6Q_15") (pintype "tri_state"))
      (node (ref "SV4") (pin "11") (pinfunction "11_11") (pintype "passive"))
    )
    (net (code "107") (name "Net-(IC10A-7Q)") (class "Default")
      (node (ref "IC10") (pin "16") (pinfunction "7Q_16") (pintype "tri_state"))
      (node (ref "SV4") (pin "13") (pinfunction "13_13") (pintype "passive"))
    )
    (net (code "108") (name "Net-(IC10A-8Q)") (class "Default")
      (node (ref "IC10") (pin "19") (pinfunction "8Q_19") (pintype "tri_state"))
      (node (ref "SV4") (pin "15") (pinfunction "15_15") (pintype "passive"))
    )
    (net (code "109") (name "Net-(IC11A-1Q)") (class "Default")
      (node (ref "IC11") (pin "2") (pinfunction "1Q_2") (pintype "tri_state"))
      (node (ref "SV6") (pin "2") (pinfunction "2_2") (pintype "passive"))
    )
    (net (code "110") (name "Net-(IC11A-2Q)") (class "Default")
      (node (ref "IC11") (pin "5") (pinfunction "2Q_5") (pintype "tri_state"))
      (node (ref "SV6") (pin "4") (pinfunction "4_4") (pintype "passive"))
    )
    (net (code "111") (name "Net-(IC11A-3Q)") (class "Default")
      (node (ref "IC11") (pin "6") (pinfunction "3Q_6") (pintype "tri_state"))
      (node (ref "SV6") (pin "6") (pinfunction "6_6") (pintype "passive"))
    )
    (net (code "112") (name "Net-(IC11A-4Q)") (class "Default")
      (node (ref "IC11") (pin "9") (pinfunction "4Q_9") (pintype "tri_state"))
      (node (ref "SV6") (pin "8") (pinfunction "8_8") (pintype "passive"))
    )
    (net (code "113") (name "Net-(IC11A-5Q)") (class "Default")
      (node (ref "IC11") (pin "12") (pinfunction "5Q_12") (pintype "tri_state"))
      (node (ref "SV6") (pin "1") (pinfunction "1_1") (pintype "passive"))
    )
    (net (code "114") (name "Net-(IC11A-6Q)") (class "Default")
      (node (ref "IC11") (pin "15") (pinfunction "6Q_15") (pintype "tri_state"))
      (node (ref "SV6") (pin "3") (pinfunction "3_3") (pintype "passive"))
    )
    (net (code "115") (name "Net-(IC11A-7Q)") (class "Default")
      (node (ref "IC11") (pin "16") (pinfunction "7Q_16") (pintype "tri_state"))
      (node (ref "SV6") (pin "5") (pinfunction "5_5") (pintype "passive"))
    )
    (net (code "116") (name "Net-(IC11A-8Q)") (class "Default")
      (node (ref "IC11") (pin "19") (pinfunction "8Q_19") (pintype "tri_state"))
      (node (ref "SV6") (pin "7") (pinfunction "7_7") (pintype "passive"))
    )
    (net (code "117") (name "Net-(IC12A-1Q)") (class "Default")
      (node (ref "IC12") (pin "2") (pinfunction "1Q_2") (pintype "tri_state"))
      (node (ref "SV6") (pin "10") (pinfunction "10_10") (pintype "passive"))
    )
    (net (code "118") (name "Net-(IC12A-2Q)") (class "Default")
      (node (ref "IC12") (pin "5") (pinfunction "2Q_5") (pintype "tri_state"))
      (node (ref "SV6") (pin "12") (pinfunction "12_12") (pintype "passive"))
    )
    (net (code "119") (name "Net-(IC12A-3Q)") (class "Default")
      (node (ref "IC12") (pin "6") (pinfunction "3Q_6") (pintype "tri_state"))
      (node (ref "SV6") (pin "14") (pinfunction "14_14") (pintype "passive"))
    )
    (net (code "120") (name "Net-(IC12A-4Q)") (class "Default")
      (node (ref "IC12") (pin "9") (pinfunction "4Q_9") (pintype "tri_state"))
      (node (ref "SV6") (pin "16") (pinfunction "16_16") (pintype "passive"))
    )
    (net (code "121") (name "Net-(IC12A-5Q)") (class "Default")
      (node (ref "IC12") (pin "12") (pinfunction "5Q_12") (pintype "tri_state"))
      (node (ref "SV6") (pin "9") (pinfunction "9_9") (pintype "passive"))
    )
    (net (code "122") (name "Net-(IC12A-6Q)") (class "Default")
      (node (ref "IC12") (pin "15") (pinfunction "6Q_15") (pintype "tri_state"))
      (node (ref "SV6") (pin "11") (pinfunction "11_11") (pintype "passive"))
    )
    (net (code "123") (name "Net-(IC12A-7Q)") (class "Default")
      (node (ref "IC12") (pin "16") (pinfunction "7Q_16") (pintype "tri_state"))
      (node (ref "SV6") (pin "13") (pinfunction "13_13") (pintype "passive"))
    )
    (net (code "124") (name "Net-(IC12A-8Q)") (class "Default")
      (node (ref "IC12") (pin "19") (pinfunction "8Q_19") (pintype "tri_state"))
      (node (ref "SV6") (pin "15") (pinfunction "15_15") (pintype "passive"))
    )
    (net (code "125") (name "Net-(IC13A-1Q)") (class "Default")
      (node (ref "IC13") (pin "2") (pinfunction "1Q_2") (pintype "tri_state"))
      (node (ref "SV7") (pin "2") (pinfunction "2_2") (pintype "passive"))
    )
    (net (code "126") (name "Net-(IC13A-2Q)") (class "Default")
      (node (ref "IC13") (pin "5") (pinfunction "2Q_5") (pintype "tri_state"))
      (node (ref "SV7") (pin "4") (pinfunction "4_4") (pintype "passive"))
    )
    (net (code "127") (name "Net-(IC13A-3Q)") (class "Default")
      (node (ref "IC13") (pin "6") (pinfunction "3Q_6") (pintype "tri_state"))
      (node (ref "SV7") (pin "6") (pinfunction "6_6") (pintype "passive"))
    )
    (net (code "128") (name "Net-(IC13A-4Q)") (class "Default")
      (node (ref "IC13") (pin "9") (pinfunction "4Q_9") (pintype "tri_state"))
      (node (ref "SV7") (pin "8") (pinfunction "8_8") (pintype "passive"))
    )
    (net (code "129") (name "Net-(IC13A-5Q)") (class "Default")
      (node (ref "IC13") (pin "12") (pinfunction "5Q_12") (pintype "tri_state"))
      (node (ref "SV7") (pin "1") (pinfunction "1_1") (pintype "passive"))
    )
    (net (code "130") (name "Net-(IC13A-6Q)") (class "Default")
      (node (ref "IC13") (pin "15") (pinfunction "6Q_15") (pintype "tri_state"))
      (node (ref "SV7") (pin "3") (pinfunction "3_3") (pintype "passive"))
    )
    (net (code "131") (name "Net-(IC13A-7Q)") (class "Default")
      (node (ref "IC13") (pin "16") (pinfunction "7Q_16") (pintype "tri_state"))
      (node (ref "SV7") (pin "5") (pinfunction "5_5") (pintype "passive"))
    )
    (net (code "132") (name "Net-(IC13A-8Q)") (class "Default")
      (node (ref "IC13") (pin "19") (pinfunction "8Q_19") (pintype "tri_state"))
      (node (ref "SV7") (pin "7") (pinfunction "7_7") (pintype "passive"))
    )
    (net (code "133") (name "Net-(IC14A-1Q)") (class "Default")
      (node (ref "IC14") (pin "2") (pinfunction "1Q_2") (pintype "tri_state"))
      (node (ref "SV7") (pin "10") (pinfunction "10_10") (pintype "passive"))
    )
    (net (code "134") (name "Net-(IC14A-2Q)") (class "Default")
      (node (ref "IC14") (pin "5") (pinfunction "2Q_5") (pintype "tri_state"))
      (node (ref "SV7") (pin "12") (pinfunction "12_12") (pintype "passive"))
    )
    (net (code "135") (name "Net-(IC14A-3Q)") (class "Default")
      (node (ref "IC14") (pin "6") (pinfunction "3Q_6") (pintype "tri_state"))
      (node (ref "SV7") (pin "14") (pinfunction "14_14") (pintype "passive"))
    )
    (net (code "136") (name "Net-(IC14A-4Q)") (class "Default")
      (node (ref "IC14") (pin "9") (pinfunction "4Q_9") (pintype "tri_state"))
      (node (ref "SV7") (pin "16") (pinfunction "16_16") (pintype "passive"))
    )
    (net (code "137") (name "Net-(IC14A-5Q)") (class "Default")
      (node (ref "IC14") (pin "12") (pinfunction "5Q_12") (pintype "tri_state"))
      (node (ref "SV7") (pin "9") (pinfunction "9_9") (pintype "passive"))
    )
    (net (code "138") (name "Net-(IC14A-6Q)") (class "Default")
      (node (ref "IC14") (pin "15") (pinfunction "6Q_15") (pintype "tri_state"))
      (node (ref "SV7") (pin "11") (pinfunction "11_11") (pintype "passive"))
    )
    (net (code "139") (name "Net-(IC14A-7Q)") (class "Default")
      (node (ref "IC14") (pin "16") (pinfunction "7Q_16") (pintype "tri_state"))
      (node (ref "SV7") (pin "13") (pinfunction "13_13") (pintype "passive"))
    )
    (net (code "140") (name "Net-(IC14A-8Q)") (class "Default")
      (node (ref "IC14") (pin "19") (pinfunction "8Q_19") (pintype "tri_state"))
      (node (ref "SV7") (pin "15") (pinfunction "15_15") (pintype "passive"))
    )
    (net (code "141") (name "Net-(IC15A-1D)") (class "Default")
      (node (ref "IC15") (pin "3") (pinfunction "1D_3") (pintype "input"))
      (node (ref "SV5") (pin "2") (pinfunction "2_2") (pintype "passive"))
    )
    (net (code "142") (name "Net-(IC15A-2D)") (class "Default")
      (node (ref "IC15") (pin "4") (pinfunction "2D_4") (pintype "input"))
      (node (ref "SV5") (pin "4") (pinfunction "4_4") (pintype "passive"))
    )
    (net (code "143") (name "Net-(IC15A-3D)") (class "Default")
      (node (ref "IC15") (pin "7") (pinfunction "3D_7") (pintype "input"))
      (node (ref "SV5") (pin "6") (pinfunction "6_6") (pintype "passive"))
    )
    (net (code "144") (name "Net-(IC15A-4D)") (class "Default")
      (node (ref "IC15") (pin "8") (pinfunction "4D_8") (pintype "input"))
      (node (ref "SV5") (pin "8") (pinfunction "8_8") (pintype "passive"))
    )
    (net (code "145") (name "Net-(IC15A-5D)") (class "Default")
      (node (ref "IC15") (pin "13") (pinfunction "5D_13") (pintype "input"))
      (node (ref "SV5") (pin "1") (pinfunction "1_1") (pintype "passive"))
    )
    (net (code "146") (name "Net-(IC15A-6D)") (class "Default")
      (node (ref "IC15") (pin "14") (pinfunction "6D_14") (pintype "input"))
      (node (ref "SV5") (pin "3") (pinfunction "3_3") (pintype "passive"))
    )
    (net (code "147") (name "Net-(IC15A-7D)") (class "Default")
      (node (ref "IC15") (pin "17") (pinfunction "7D_17") (pintype "input"))
      (node (ref "SV5") (pin "5") (pinfunction "5_5") (pintype "passive"))
    )
    (net (code "148") (name "Net-(IC15A-8D)") (class "Default")
      (node (ref "IC15") (pin "18") (pinfunction "8D_18") (pintype "input"))
      (node (ref "SV5") (pin "7") (pinfunction "7_7") (pintype "passive"))
    )
    (net (code "149") (name "Net-(IC16A-1D)") (class "Default")
      (node (ref "IC16") (pin "3") (pinfunction "1D_3") (pintype "input"))
      (node (ref "SV5") (pin "10") (pinfunction "10_10") (pintype "passive"))
    )
    (net (code "150") (name "Net-(IC16A-2D)") (class "Default")
      (node (ref "IC16") (pin "4") (pinfunction "2D_4") (pintype "input"))
      (node (ref "SV5") (pin "12") (pinfunction "12_12") (pintype "passive"))
    )
    (net (code "151") (name "Net-(IC16A-3D)") (class "Default")
      (node (ref "IC16") (pin "7") (pinfunction "3D_7") (pintype "input"))
      (node (ref "SV5") (pin "14") (pinfunction "14_14") (pintype "passive"))
    )
    (net (code "152") (name "Net-(IC16A-4D)") (class "Default")
      (node (ref "IC16") (pin "8") (pinfunction "4D_8") (pintype "input"))
      (node (ref "SV5") (pin "16") (pinfunction "16_16") (pintype "passive"))
    )
    (net (code "153") (name "Net-(IC16A-5D)") (class "Default")
      (node (ref "IC16") (pin "13") (pinfunction "5D_13") (pintype "input"))
      (node (ref "SV5") (pin "9") (pinfunction "9_9") (pintype "passive"))
    )
    (net (code "154") (name "Net-(IC16A-6D)") (class "Default")
      (node (ref "IC16") (pin "14") (pinfunction "6D_14") (pintype "input"))
      (node (ref "SV5") (pin "11") (pinfunction "11_11") (pintype "passive"))
    )
    (net (code "155") (name "Net-(IC16A-7D)") (class "Default")
      (node (ref "IC16") (pin "17") (pinfunction "7D_17") (pintype "input"))
      (node (ref "SV5") (pin "13") (pinfunction "13_13") (pintype "passive"))
    )
    (net (code "156") (name "Net-(IC16A-8D)") (class "Default")
      (node (ref "IC16") (pin "18") (pinfunction "8D_18") (pintype "input"))
      (node (ref "SV5") (pin "15") (pinfunction "15_15") (pintype "passive"))
    )
    (net (code "157") (name "Net-(IC17A-EXTAL)") (class "Default")
      (node (ref "C2") (pin "1") (pinfunction "1_1") (pintype "passive"))
      (node (ref "IC17") (pin "39") (pinfunction "EXTAL_39") (pintype "input"))
      (node (ref "Q1") (pin "1") (pinfunction "1_1") (pintype "passive"))
    )
    (net (code "158") (name "Net-(IC17A-XTAL)") (class "Default")
      (node (ref "C1") (pin "2") (pinfunction "2_2") (pintype "passive"))
      (node (ref "IC17") (pin "38") (pinfunction "XTAL_38") (pintype "input"))
      (node (ref "Q1") (pin "2") (pinfunction "2_2") (pintype "passive"))
    )
    (net (code "159") (name "Net-(IC18A-I0)") (class "Default")
      (node (ref "C3") (pin "1") (pinfunction "1_1") (pintype "passive"))
      (node (ref "IC18") (pin "1") (pinfunction "I0_1") (pintype "input"))
      (node (ref "R1") (pin "1") (pinfunction "1_1") (pintype "passive"))
    )
    (net (code "160") (name "Net-(IC18A-I1)") (class "Default")
      (node (ref "IC18") (pin "2") (pinfunction "I1_2") (pintype "input"))
      (node (ref "R2") (pin "1") (pinfunction "1_1") (pintype "passive"))
      (node (ref "S1") (pin "A") (pinfunction "A_A") (pintype "passive"))
      (node (ref "S1") (pin "A1") (pinfunction "A1_A1") (pintype "passive"))
    )
    (net (code "161") (name "Net-(IC18A-O)") (class "Default")
      (node (ref "IC18") (pin "3") (pinfunction "O_3") (pintype "output"))
      (node (ref "IC18") (pin "4") (pinfunction "I0_4") (pintype "input"))
      (node (ref "IC18") (pin "5") (pinfunction "I1_5") (pintype "input"))
    )
    (net (code "162") (name "Net-(IC18C-O)") (class "Default")
      (node (ref "IC18") (pin "8") (pinfunction "O_8") (pintype "output"))
      (node (ref "IC28") (pin "4") (pinfunction "G2A_4") (pintype "input"))
    )
    (net (code "163") (name "Net-(IC18D-I0)") (class "Default")
      (node (ref "IC18") (pin "12") (pinfunction "I0_12") (pintype "input"))
      (node (ref "IC18") (pin "13") (pinfunction "I1_13") (pintype "input"))
      (node (ref "IC21") (pin "5") (pinfunction "RTS_5") (pintype "output"))
    )
    (net (code "164") (name "Net-(IC18D-O)") (class "Default")
      (node (ref "IC18") (pin "11") (pinfunction "O_11") (pintype "output"))
      (node (ref "LED1") (pin "K") (pinfunction "C_K") (pintype "passive"))
    )
    (net (code "165") (name "Net-(IC19A-G2B)") (class "Default")
      (node (ref "IC19") (pin "5") (pinfunction "G2B_5") (pintype "input"))
      (node (ref "IC28") (pin "15") (pinfunction "Y0_15") (pintype "output"))
    )
    (net (code "166") (name "Net-(IC20A-C1+)") (class "Default")
      (node (ref "C8") (pin "1") (pinfunction "1_1") (pintype "passive"))
      (node (ref "IC20") (pin "1") (pinfunction "C1+_1") (pintype "bidirectional"))
    )
    (net (code "167") (name "Net-(IC20A-C1-)") (class "Default")
      (node (ref "C8") (pin "2") (pinfunction "2_2") (pintype "passive"))
      (node (ref "IC20") (pin "3") (pinfunction "C1-_3") (pintype "bidirectional"))
    )
    (net (code "168") (name "Net-(IC20A-C2+)") (class "Default")
      (node (ref "C9") (pin "1") (pinfunction "1_1") (pintype "passive"))
      (node (ref "IC20") (pin "4") (pinfunction "C2+_4") (pintype "bidirectional"))
    )
    (net (code "169") (name "Net-(IC20A-C2-)") (class "Default")
      (node (ref "C9") (pin "2") (pinfunction "2_2") (pintype "passive"))
      (node (ref "IC20") (pin "5") (pinfunction "C2-_5") (pintype "bidirectional"))
    )
    (net (code "170") (name "Net-(IC20A-R2IN)") (class "Default")
      (node (ref "IC20") (pin "7") (pinfunction "T2OUT_7") (pintype "output"))
      (node (ref "IC20") (pin "8") (pinfunction "R2IN_8") (pintype "input"))
    )
    (net (code "171") (name "Net-(IC20A-V+)") (class "Default")
      (node (ref "C10") (pin "2") (pinfunction "2_2") (pintype "passive"))
      (node (ref "IC20") (pin "2") (pinfunction "V+_2") (pintype "bidirectional"))
    )
    (net (code "172") (name "Net-(IC20A-V-)") (class "Default")
      (node (ref "C11") (pin "1") (pinfunction "1_1") (pintype "passive"))
      (node (ref "IC20") (pin "6") (pinfunction "V-_6") (pintype "bidirectional"))
    )
    (net (code "173") (name "Net-(IC21A-CTS)") (class "Default")
      (node (ref "IC21") (pin "24") (pinfunction "CTS_24") (pintype "input"))
      (node (ref "R13") (pin "2") (pinfunction "2_2") (pintype "passive"))
      (node (ref "S2") (pin "B") (pinfunction "B_B") (pintype "passive"))
    )
    (net (code "174") (name "Net-(IC21A-RXCLK)") (class "Default")
      (node (ref "IC21") (pin "3") (pinfunction "RXCLK_3") (pintype "input"))
      (node (ref "IC21") (pin "4") (pinfunction "TXCLK_4") (pintype "input"))
      (node (ref "IC27") (pin "5") (pinfunction "Q_5") (pintype "output"))
    )
    (net (code "175") (name "Net-(IC24A-CA1)") (class "Default")
      (node (ref "IC24") (pin "40") (pinfunction "CA1_40") (pintype "input"))
      (node (ref "IC27") (pin "9") (pinfunction "Q_9") (pintype "output"))
    )
    (net (code "176") (name "Net-(IC24A-CA2)") (class "Default")
      (node (ref "IC24") (pin "39") (pinfunction "CA2_39") (pintype "bidirectional"))
      (node (ref "IC25") (pin "1") (pinfunction "DIR_1") (pintype "input"))
    )
    (net (code "177") (name "Net-(IC24A-CB2)") (class "Default")
      (node (ref "IC24") (pin "19") (pinfunction "CB2_19") (pintype "bidirectional"))
      (node (ref "IC26") (pin "1") (pinfunction "DIR_1") (pintype "input"))
    )
    (net (code "178") (name "Net-(IC24A-PA0)") (class "Default")
      (node (ref "IC24") (pin "2") (pinfunction "PA0_2") (pintype "bidirectional"))
      (node (ref "IC25") (pin "2") (pinfunction "A1_2") (pintype "bidirectional"))
    )
    (net (code "179") (name "Net-(IC24A-PA1)") (class "Default")
      (node (ref "IC24") (pin "3") (pinfunction "PA1_3") (pintype "bidirectional"))
      (node (ref "IC25") (pin "3") (pinfunction "A2_3") (pintype "bidirectional"))
    )
    (net (code "180") (name "Net-(IC24A-PA2)") (class "Default")
      (node (ref "IC24") (pin "4") (pinfunction "PA2_4") (pintype "bidirectional"))
      (node (ref "IC25") (pin "4") (pinfunction "A3_4") (pintype "bidirectional"))
    )
    (net (code "181") (name "Net-(IC24A-PA3)") (class "Default")
      (node (ref "IC24") (pin "5") (pinfunction "PA3_5") (pintype "bidirectional"))
      (node (ref "IC25") (pin "5") (pinfunction "A4_5") (pintype "bidirectional"))
    )
    (net (code "182") (name "Net-(IC24A-PA4)") (class "Default")
      (node (ref "IC24") (pin "6") (pinfunction "PA4_6") (pintype "bidirectional"))
      (node (ref "IC25") (pin "6") (pinfunction "A5_6") (pintype "bidirectional"))
    )
    (net (code "183") (name "Net-(IC24A-PA5)") (class "Default")
      (node (ref "IC24") (pin "7") (pinfunction "PA5_7") (pintype "bidirectional"))
      (node (ref "IC25") (pin "7") (pinfunction "A6_7") (pintype "bidirectional"))
    )
    (net (code "184") (name "Net-(IC24A-PA6)") (class "Default")
      (node (ref "IC24") (pin "8") (pinfunction "PA6_8") (pintype "bidirectional"))
      (node (ref "IC25") (pin "8") (pinfunction "A7_8") (pintype "bidirectional"))
    )
    (net (code "185") (name "Net-(IC24A-PA7)") (class "Default")
      (node (ref "IC24") (pin "9") (pinfunction "PA7_9") (pintype "bidirectional"))
      (node (ref "IC25") (pin "9") (pinfunction "A8_9") (pintype "bidirectional"))
    )
    (net (code "186") (name "Net-(IC24A-PB0)") (class "Default")
      (node (ref "IC24") (pin "10") (pinfunction "PB0_10") (pintype "bidirectional"))
      (node (ref "IC26") (pin "2") (pinfunction "A1_2") (pintype "bidirectional"))
    )
    (net (code "187") (name "Net-(IC24A-PB1)") (class "Default")
      (node (ref "IC24") (pin "11") (pinfunction "PB1_11") (pintype "bidirectional"))
      (node (ref "IC26") (pin "3") (pinfunction "A2_3") (pintype "bidirectional"))
    )
    (net (code "188") (name "Net-(IC24A-PB2)") (class "Default")
      (node (ref "IC24") (pin "12") (pinfunction "PB2_12") (pintype "bidirectional"))
      (node (ref "IC26") (pin "4") (pinfunction "A3_4") (pintype "bidirectional"))
    )
    (net (code "189") (name "Net-(IC24A-PB3)") (class "Default")
      (node (ref "IC24") (pin "13") (pinfunction "PB3_13") (pintype "bidirectional"))
      (node (ref "IC26") (pin "5") (pinfunction "A4_5") (pintype "bidirectional"))
    )
    (net (code "190") (name "Net-(IC24A-PB4)") (class "Default")
      (node (ref "IC24") (pin "14") (pinfunction "PB4_14") (pintype "bidirectional"))
      (node (ref "IC26") (pin "6") (pinfunction "A5_6") (pintype "bidirectional"))
    )
    (net (code "191") (name "Net-(IC24A-PB5)") (class "Default")
      (node (ref "IC24") (pin "15") (pinfunction "PB5_15") (pintype "bidirectional"))
      (node (ref "IC26") (pin "7") (pinfunction "A6_7") (pintype "bidirectional"))
    )
    (net (code "192") (name "Net-(IC24A-PB6)") (class "Default")
      (node (ref "IC24") (pin "16") (pinfunction "PB6_16") (pintype "bidirectional"))
      (node (ref "IC26") (pin "8") (pinfunction "A7_8") (pintype "bidirectional"))
    )
    (net (code "193") (name "Net-(IC24A-PB7)") (class "Default")
      (node (ref "IC24") (pin "17") (pinfunction "PB7_17") (pintype "bidirectional"))
      (node (ref "IC26") (pin "9") (pinfunction "A8_9") (pintype "bidirectional"))
    )
    (net (code "194") (name "Net-(IC27A-CV)") (class "Default")
      (node (ref "C7") (pin "1") (pinfunction "1_1") (pintype "passive"))
      (node (ref "IC27") (pin "3") (pinfunction "CV_3") (pintype "input"))
    )
    (net (code "195") (name "Net-(IC27A-DIS)") (class "Default")
      (node (ref "IC27") (pin "1") (pinfunction "DIS_1") (pintype "input"))
      (node (ref "R10") (pin "2") (pinfunction "2_2") (pintype "passive"))
      (node (ref "R9") (pin "1") (pinfunction "1_1") (pintype "passive"))
    )
    (net (code "196") (name "Net-(IC27A-THR)") (class "Default")
      (node (ref "C6") (pin "1") (pinfunction "1_1") (pintype "passive"))
      (node (ref "IC27") (pin "2") (pinfunction "THR_2") (pintype "input"))
      (node (ref "IC27") (pin "6") (pinfunction "TR_6") (pintype "input"))
      (node (ref "R11") (pin "A") (pinfunction "A_A") (pintype "passive"))
    )
    (net (code "197") (name "Net-(IC27B-CV)") (class "Default")
      (node (ref "C5") (pin "1") (pinfunction "1_1") (pintype "passive"))
      (node (ref "IC27") (pin "11") (pinfunction "CV_11") (pintype "input"))
    )
    (net (code "198") (name "Net-(IC27B-DIS)") (class "Default")
      (node (ref "IC27") (pin "13") (pinfunction "DIS_13") (pintype "input"))
      (node (ref "R3") (pin "1") (pinfunction "1_1") (pintype "passive"))
      (node (ref "R4") (pin "2") (pinfunction "2_2") (pintype "passive"))
    )
    (net (code "199") (name "Net-(IC27B-THR)") (class "Default")
      (node (ref "C4") (pin "1") (pinfunction "1_1") (pintype "passive"))
      (node (ref "IC27") (pin "12") (pinfunction "THR_12") (pintype "input"))
      (node (ref "IC27") (pin "8") (pinfunction "TR_8") (pintype "input"))
      (node (ref "R4") (pin "1") (pinfunction "1_1") (pintype "passive"))
    )
    (net (code "200") (name "Net-(LED1-PadA)") (class "Default")
      (node (ref "LED1") (pin "A") (pinfunction "A_A") (pintype "passive"))
      (node (ref "R12") (pin "1") (pinfunction "1_1") (pintype "passive"))
    )
    (net (code "201") (name "Net-(R10-Pad1)") (class "Default")
      (node (ref "R10") (pin "1") (pinfunction "1_1") (pintype "passive"))
      (node (ref "R11") (pin "E") (pinfunction "E_E") (pintype "passive"))
    )
    (net (code "202") (name "Net-(X1-Pad4)") (class "Default")
      (node (ref "X1") (pin "4") (pinfunction "4_4") (pintype "passive"))
      (node (ref "X1") (pin "6") (pinfunction "6_6") (pintype "passive"))
    )
    (net (code "203") (name "Net-(X1-Pad5)") (class "Default")
      (node (ref "X1") (pin "5") (pinfunction "5_5") (pintype "passive"))
      (node (ref "X1") (pin "G1") (pinfunction "G1_G1") (pintype "passive"))
      (node (ref "X1") (pin "G2") (pinfunction "G2_G2") (pintype "passive"))
    )
    (net (code "204") (name "Net-(X1-Pad7)") (class "Default")
      (node (ref "X1") (pin "7") (pinfunction "7_7") (pintype "passive"))
      (node (ref "X1") (pin "8") (pinfunction "8_8") (pintype "passive"))
    )
    (net (code "205") (name "OUT00") (class "Default")
      (node (ref "IC1") (pin "1") (pinfunction "0_1") (pintype "output"))
      (node (ref "IC6") (pin "11") (pinfunction "CLK_11") (pintype "input"))
    )
    (net (code "206") (name "OUT01") (class "Default")
      (node (ref "IC1") (pin "2") (pinfunction "1_2") (pintype "output"))
      (node (ref "IC7") (pin "11") (pinfunction "CLK_11") (pintype "input"))
    )
    (net (code "207") (name "OUT02") (class "Default")
      (node (ref "IC1") (pin "3") (pinfunction "2_3") (pintype "output"))
      (node (ref "IC8") (pin "11") (pinfunction "CLK_11") (pintype "input"))
    )
    (net (code "208") (name "OUT03") (class "Default")
      (node (ref "IC1") (pin "4") (pinfunction "3_4") (pintype "output"))
      (node (ref "IC10") (pin "11") (pinfunction "CLK_11") (pintype "input"))
    )
    (net (code "209") (name "OUT04") (class "Default")
      (node (ref "IC1") (pin "5") (pinfunction "4_5") (pintype "output"))
      (node (ref "IC11") (pin "11") (pinfunction "CLK_11") (pintype "input"))
    )
    (net (code "210") (name "OUT05") (class "Default")
      (node (ref "IC1") (pin "6") (pinfunction "5_6") (pintype "output"))
      (node (ref "IC12") (pin "11") (pinfunction "CLK_11") (pintype "input"))
    )
    (net (code "211") (name "OUT06") (class "Default")
      (node (ref "IC1") (pin "7") (pinfunction "6_7") (pintype "output"))
      (node (ref "IC13") (pin "11") (pinfunction "CLK_11") (pintype "input"))
    )
    (net (code "212") (name "OUT07") (class "Default")
      (node (ref "IC1") (pin "8") (pinfunction "7_8") (pintype "output"))
      (node (ref "IC14") (pin "11") (pinfunction "CLK_11") (pintype "input"))
    )
    (net (code "213") (name "OUT08") (class "Default")
      (node (ref "IC1") (pin "9") (pinfunction "8_9") (pintype "output"))
    )
    (net (code "214") (name "OUT09") (class "Default")
      (node (ref "IC1") (pin "10") (pinfunction "9_10") (pintype "output"))
    )
    (net (code "215") (name "OUT10") (class "Default")
      (node (ref "IC1") (pin "11") (pinfunction "10_11") (pintype "output"))
    )
    (net (code "216") (name "OUT11") (class "Default")
      (node (ref "IC1") (pin "13") (pinfunction "11_13") (pintype "output"))
    )
    (net (code "217") (name "OUT12") (class "Default")
      (node (ref "IC1") (pin "14") (pinfunction "12_14") (pintype "output"))
    )
    (net (code "218") (name "OUT13") (class "Default")
      (node (ref "IC1") (pin "15") (pinfunction "13_15") (pintype "output"))
    )
    (net (code "219") (name "OUT14") (class "Default")
      (node (ref "IC1") (pin "16") (pinfunction "14_16") (pintype "output"))
    )
    (net (code "220") (name "OUT15") (class "Default")
      (node (ref "IC1") (pin "17") (pinfunction "15_17") (pintype "output"))
    )
    (net (code "221") (name "PIA-A0") (class "Default")
      (node (ref "IC10") (pin "3") (pinfunction "1D_3") (pintype "input"))
      (node (ref "IC11") (pin "3") (pinfunction "1D_3") (pintype "input"))
      (node (ref "IC12") (pin "3") (pinfunction "1D_3") (pintype "input"))
      (node (ref "IC13") (pin "3") (pinfunction "1D_3") (pintype "input"))
      (node (ref "IC14") (pin "3") (pinfunction "1D_3") (pintype "input"))
      (node (ref "IC15") (pin "2") (pinfunction "1Q_2") (pintype "tri_state"))
      (node (ref "IC16") (pin "2") (pinfunction "1Q_2") (pintype "tri_state"))
      (node (ref "IC2") (pin "2") (pinfunction "1Q_2") (pintype "tri_state"))
      (node (ref "IC25") (pin "18") (pinfunction "B1_18") (pintype "bidirectional"))
      (node (ref "IC3") (pin "2") (pinfunction "1Q_2") (pintype "tri_state"))
      (node (ref "IC4") (pin "2") (pinfunction "1Q_2") (pintype "tri_state"))
      (node (ref "IC6") (pin "3") (pinfunction "1D_3") (pintype "input"))
      (node (ref "IC7") (pin "3") (pinfunction "1D_3") (pintype "input"))
      (node (ref "IC8") (pin "3") (pinfunction "1D_3") (pintype "input"))
      (node (ref "IC9") (pin "2") (pinfunction "1Q_2") (pintype "tri_state"))
    )
    (net (code "222") (name "PIA-A1") (class "Default")
      (node (ref "IC10") (pin "4") (pinfunction "2D_4") (pintype "input"))
      (node (ref "IC11") (pin "4") (pinfunction "2D_4") (pintype "input"))
      (node (ref "IC12") (pin "4") (pinfunction "2D_4") (pintype "input"))
      (node (ref "IC13") (pin "4") (pinfunction "2D_4") (pintype "input"))
      (node (ref "IC14") (pin "4") (pinfunction "2D_4") (pintype "input"))
      (node (ref "IC15") (pin "5") (pinfunction "2Q_5") (pintype "tri_state"))
      (node (ref "IC16") (pin "5") (pinfunction "2Q_5") (pintype "tri_state"))
      (node (ref "IC2") (pin "5") (pinfunction "2Q_5") (pintype "tri_state"))
      (node (ref "IC25") (pin "17") (pinfunction "B2_17") (pintype "bidirectional"))
      (node (ref "IC3") (pin "5") (pinfunction "2Q_5") (pintype "tri_state"))
      (node (ref "IC4") (pin "5") (pinfunction "2Q_5") (pintype "tri_state"))
      (node (ref "IC6") (pin "4") (pinfunction "2D_4") (pintype "input"))
      (node (ref "IC7") (pin "4") (pinfunction "2D_4") (pintype "input"))
      (node (ref "IC8") (pin "4") (pinfunction "2D_4") (pintype "input"))
      (node (ref "IC9") (pin "5") (pinfunction "2Q_5") (pintype "tri_state"))
    )
    (net (code "223") (name "PIA-A2") (class "Default")
      (node (ref "IC10") (pin "7") (pinfunction "3D_7") (pintype "input"))
      (node (ref "IC11") (pin "7") (pinfunction "3D_7") (pintype "input"))
      (node (ref "IC12") (pin "7") (pinfunction "3D_7") (pintype "input"))
      (node (ref "IC13") (pin "7") (pinfunction "3D_7") (pintype "input"))
      (node (ref "IC14") (pin "7") (pinfunction "3D_7") (pintype "input"))
      (node (ref "IC15") (pin "6") (pinfunction "3Q_6") (pintype "tri_state"))
      (node (ref "IC16") (pin "6") (pinfunction "3Q_6") (pintype "tri_state"))
      (node (ref "IC2") (pin "6") (pinfunction "3Q_6") (pintype "tri_state"))
      (node (ref "IC25") (pin "16") (pinfunction "B3_16") (pintype "bidirectional"))
      (node (ref "IC3") (pin "6") (pinfunction "3Q_6") (pintype "tri_state"))
      (node (ref "IC4") (pin "6") (pinfunction "3Q_6") (pintype "tri_state"))
      (node (ref "IC6") (pin "7") (pinfunction "3D_7") (pintype "input"))
      (node (ref "IC7") (pin "7") (pinfunction "3D_7") (pintype "input"))
      (node (ref "IC8") (pin "7") (pinfunction "3D_7") (pintype "input"))
      (node (ref "IC9") (pin "6") (pinfunction "3Q_6") (pintype "tri_state"))
    )
    (net (code "224") (name "PIA-A3") (class "Default")
      (node (ref "IC10") (pin "8") (pinfunction "4D_8") (pintype "input"))
      (node (ref "IC11") (pin "8") (pinfunction "4D_8") (pintype "input"))
      (node (ref "IC12") (pin "8") (pinfunction "4D_8") (pintype "input"))
      (node (ref "IC13") (pin "8") (pinfunction "4D_8") (pintype "input"))
      (node (ref "IC14") (pin "8") (pinfunction "4D_8") (pintype "input"))
      (node (ref "IC15") (pin "9") (pinfunction "4Q_9") (pintype "tri_state"))
      (node (ref "IC16") (pin "9") (pinfunction "4Q_9") (pintype "tri_state"))
      (node (ref "IC2") (pin "9") (pinfunction "4Q_9") (pintype "tri_state"))
      (node (ref "IC25") (pin "15") (pinfunction "B4_15") (pintype "bidirectional"))
      (node (ref "IC3") (pin "9") (pinfunction "4Q_9") (pintype "tri_state"))
      (node (ref "IC4") (pin "9") (pinfunction "4Q_9") (pintype "tri_state"))
      (node (ref "IC6") (pin "8") (pinfunction "4D_8") (pintype "input"))
      (node (ref "IC7") (pin "8") (pinfunction "4D_8") (pintype "input"))
      (node (ref "IC8") (pin "8") (pinfunction "4D_8") (pintype "input"))
      (node (ref "IC9") (pin "9") (pinfunction "4Q_9") (pintype "tri_state"))
    )
    (net (code "225") (name "PIA-A4") (class "Default")
      (node (ref "IC10") (pin "13") (pinfunction "5D_13") (pintype "input"))
      (node (ref "IC11") (pin "13") (pinfunction "5D_13") (pintype "input"))
      (node (ref "IC12") (pin "13") (pinfunction "5D_13") (pintype "input"))
      (node (ref "IC13") (pin "13") (pinfunction "5D_13") (pintype "input"))
      (node (ref "IC14") (pin "13") (pinfunction "5D_13") (pintype "input"))
      (node (ref "IC15") (pin "12") (pinfunction "5Q_12") (pintype "tri_state"))
      (node (ref "IC16") (pin "12") (pinfunction "5Q_12") (pintype "tri_state"))
      (node (ref "IC2") (pin "12") (pinfunction "5Q_12") (pintype "tri_state"))
      (node (ref "IC25") (pin "14") (pinfunction "B5_14") (pintype "bidirectional"))
      (node (ref "IC3") (pin "12") (pinfunction "5Q_12") (pintype "tri_state"))
      (node (ref "IC4") (pin "12") (pinfunction "5Q_12") (pintype "tri_state"))
      (node (ref "IC6") (pin "13") (pinfunction "5D_13") (pintype "input"))
      (node (ref "IC7") (pin "13") (pinfunction "5D_13") (pintype "input"))
      (node (ref "IC8") (pin "13") (pinfunction "5D_13") (pintype "input"))
      (node (ref "IC9") (pin "12") (pinfunction "5Q_12") (pintype "tri_state"))
    )
    (net (code "226") (name "PIA-A5") (class "Default")
      (node (ref "IC10") (pin "14") (pinfunction "6D_14") (pintype "input"))
      (node (ref "IC11") (pin "14") (pinfunction "6D_14") (pintype "input"))
      (node (ref "IC12") (pin "14") (pinfunction "6D_14") (pintype "input"))
      (node (ref "IC13") (pin "14") (pinfunction "6D_14") (pintype "input"))
      (node (ref "IC14") (pin "14") (pinfunction "6D_14") (pintype "input"))
      (node (ref "IC15") (pin "15") (pinfunction "6Q_15") (pintype "tri_state"))
      (node (ref "IC16") (pin "15") (pinfunction "6Q_15") (pintype "tri_state"))
      (node (ref "IC2") (pin "15") (pinfunction "6Q_15") (pintype "tri_state"))
      (node (ref "IC25") (pin "13") (pinfunction "B6_13") (pintype "bidirectional"))
      (node (ref "IC3") (pin "15") (pinfunction "6Q_15") (pintype "tri_state"))
      (node (ref "IC4") (pin "15") (pinfunction "6Q_15") (pintype "tri_state"))
      (node (ref "IC6") (pin "14") (pinfunction "6D_14") (pintype "input"))
      (node (ref "IC7") (pin "14") (pinfunction "6D_14") (pintype "input"))
      (node (ref "IC8") (pin "14") (pinfunction "6D_14") (pintype "input"))
      (node (ref "IC9") (pin "15") (pinfunction "6Q_15") (pintype "tri_state"))
    )
    (net (code "227") (name "PIA-A6") (class "Default")
      (node (ref "IC10") (pin "17") (pinfunction "7D_17") (pintype "input"))
      (node (ref "IC11") (pin "17") (pinfunction "7D_17") (pintype "input"))
      (node (ref "IC12") (pin "17") (pinfunction "7D_17") (pintype "input"))
      (node (ref "IC13") (pin "17") (pinfunction "7D_17") (pintype "input"))
      (node (ref "IC14") (pin "17") (pinfunction "7D_17") (pintype "input"))
      (node (ref "IC15") (pin "16") (pinfunction "7Q_16") (pintype "tri_state"))
      (node (ref "IC16") (pin "16") (pinfunction "7Q_16") (pintype "tri_state"))
      (node (ref "IC2") (pin "16") (pinfunction "7Q_16") (pintype "tri_state"))
      (node (ref "IC25") (pin "12") (pinfunction "B7_12") (pintype "bidirectional"))
      (node (ref "IC3") (pin "16") (pinfunction "7Q_16") (pintype "tri_state"))
      (node (ref "IC4") (pin "16") (pinfunction "7Q_16") (pintype "tri_state"))
      (node (ref "IC6") (pin "17") (pinfunction "7D_17") (pintype "input"))
      (node (ref "IC7") (pin "17") (pinfunction "7D_17") (pintype "input"))
      (node (ref "IC8") (pin "17") (pinfunction "7D_17") (pintype "input"))
      (node (ref "IC9") (pin "16") (pinfunction "7Q_16") (pintype "tri_state"))
    )
    (net (code "228") (name "PIA-A7") (class "Default")
      (node (ref "IC10") (pin "18") (pinfunction "8D_18") (pintype "input"))
      (node (ref "IC11") (pin "18") (pinfunction "8D_18") (pintype "input"))
      (node (ref "IC12") (pin "18") (pinfunction "8D_18") (pintype "input"))
      (node (ref "IC13") (pin "18") (pinfunction "8D_18") (pintype "input"))
      (node (ref "IC14") (pin "18") (pinfunction "8D_18") (pintype "input"))
      (node (ref "IC15") (pin "19") (pinfunction "8Q_19") (pintype "tri_state"))
      (node (ref "IC16") (pin "19") (pinfunction "8Q_19") (pintype "tri_state"))
      (node (ref "IC2") (pin "19") (pinfunction "8Q_19") (pintype "tri_state"))
      (node (ref "IC25") (pin "11") (pinfunction "B8_11") (pintype "bidirectional"))
      (node (ref "IC3") (pin "19") (pinfunction "8Q_19") (pintype "tri_state"))
      (node (ref "IC4") (pin "19") (pinfunction "8Q_19") (pintype "tri_state"))
      (node (ref "IC6") (pin "18") (pinfunction "8D_18") (pintype "input"))
      (node (ref "IC7") (pin "18") (pinfunction "8D_18") (pintype "input"))
      (node (ref "IC8") (pin "18") (pinfunction "8D_18") (pintype "input"))
      (node (ref "IC9") (pin "19") (pinfunction "8Q_19") (pintype "tri_state"))
    )
    (net (code "229") (name "PIA-B0") (class "Default")
      (node (ref "IC1") (pin "23") (pinfunction "A_23") (pintype "input"))
      (node (ref "IC26") (pin "18") (pinfunction "B1_18") (pintype "bidirectional"))
      (node (ref "IC5") (pin "23") (pinfunction "A_23") (pintype "input"))
    )
    (net (code "230") (name "PIA-B1") (class "Default")
      (node (ref "IC1") (pin "22") (pinfunction "B_22") (pintype "input"))
      (node (ref "IC26") (pin "17") (pinfunction "B2_17") (pintype "bidirectional"))
      (node (ref "IC5") (pin "22") (pinfunction "B_22") (pintype "input"))
    )
    (net (code "231") (name "PIA-B2") (class "Default")
      (node (ref "IC1") (pin "21") (pinfunction "C_21") (pintype "input"))
      (node (ref "IC26") (pin "16") (pinfunction "B3_16") (pintype "bidirectional"))
      (node (ref "IC5") (pin "21") (pinfunction "C_21") (pintype "input"))
    )
    (net (code "232") (name "PIA-B3") (class "Default")
      (node (ref "IC1") (pin "20") (pinfunction "D_20") (pintype "input"))
      (node (ref "IC26") (pin "15") (pinfunction "B4_15") (pintype "bidirectional"))
      (node (ref "IC5") (pin "20") (pinfunction "D_20") (pintype "input"))
    )
    (net (code "233") (name "PIA-B4") (class "Default")
      (node (ref "IC26") (pin "14") (pinfunction "B5_14") (pintype "bidirectional"))
      (node (ref "IC5") (pin "18") (pinfunction "G1_18") (pintype "input"))
    )
    (net (code "234") (name "PIA-B5") (class "Default")
      (node (ref "IC1") (pin "18") (pinfunction "G1_18") (pintype "input"))
      (node (ref "IC26") (pin "13") (pinfunction "B6_13") (pintype "bidirectional"))
    )
    (net (code "235") (name "PIA-B6") (class "Default")
      (node (ref "IC26") (pin "12") (pinfunction "B7_12") (pintype "bidirectional"))
    )
    (net (code "236") (name "PIA-B7") (class "Default")
      (node (ref "IC26") (pin "11") (pinfunction "B8_11") (pintype "bidirectional"))
    )
    (net (code "237") (name "RX") (class "Default")
      (node (ref "IC20") (pin "12") (pinfunction "R1OUT_12") (pintype "output"))
      (node (ref "IC21") (pin "2") (pinfunction "RXDATA_2") (pintype "input"))
    )
    (net (code "238") (name "RXD") (class "Default")
      (node (ref "IC20") (pin "13") (pinfunction "R1IN_13") (pintype "input"))
      (node (ref "X1") (pin "2") (pinfunction "2_2") (pintype "passive"))
    )
    (net (code "239") (name "R{slash}~{W}") (class "Default")
      (node (ref "IC17") (pin "34") (pinfunction "R/~{W}_34") (pintype "output"))
      (node (ref "IC21") (pin "13") (pinfunction "R/~{W}_13") (pintype "input"))
      (node (ref "IC22") (pin "27") (pinfunction "~{PGM}_27") (pintype "input"))
      (node (ref "IC24") (pin "21") (pinfunction "R/~{W}_21") (pintype "input"))
    )
    (net (code "240") (name "TX") (class "Default")
      (node (ref "IC20") (pin "11") (pinfunction "T1IN_11") (pintype "input"))
      (node (ref "IC21") (pin "6") (pinfunction "TXDATA_6") (pintype "output"))
    )
    (net (code "241") (name "TXD") (class "Default")
      (node (ref "IC20") (pin "14") (pinfunction "T1OUT_14") (pintype "output"))
      (node (ref "X1") (pin "3") (pinfunction "3_3") (pintype "passive"))
    )
    (net (code "242") (name "VCC") (class "Default")
      (node (ref "C10") (pin "1") (pinfunction "1_1") (pintype "passive"))
      (node (ref "IC15") (pin "11") (pinfunction "ENC_11") (pintype "input"))
      (node (ref "IC16") (pin "11") (pinfunction "ENC_11") (pintype "input"))
      (node (ref "IC17") (pin "35") (pinfunction "VCCSTB_35") (pintype "input"))
      (node (ref "IC17") (pin "36") (pinfunction "RE_36") (pintype "input"))
      (node (ref "IC17") (pin "8") (pinfunction "VCC_8") (pintype "power_in"))
      (node (ref "IC2") (pin "11") (pinfunction "ENC_11") (pintype "input"))
      (node (ref "IC21") (pin "10") (pinfunction "CS1_10") (pintype "input"))
      (node (ref "IC21") (pin "12") (pinfunction "VCC_12") (pintype "power_in"))
      (node (ref "IC21") (pin "8") (pinfunction "CS0_8") (pintype "input"))
      (node (ref "IC22") (pin "1") (pinfunction "VPP_1") (pintype "input"))
      (node (ref "IC23") (pin "1") (pinfunction "VPP_1") (pintype "input"))
      (node (ref "IC23") (pin "27") (pinfunction "~{PGM}_27") (pintype "input"))
      (node (ref "IC24") (pin "20") (pinfunction "VCC_20") (pintype "power_in"))
      (node (ref "IC24") (pin "22") (pinfunction "CS0_22") (pintype "input"))
      (node (ref "IC24") (pin "24") (pinfunction "CS1_24") (pintype "input"))
      (node (ref "IC27") (pin "10") (pinfunction "R_10") (pintype "input"))
      (node (ref "IC27") (pin "14") (pinfunction "V+_14") (pintype "power_in"))
      (node (ref "IC27") (pin "4") (pinfunction "R_4") (pintype "input"))
      (node (ref "IC28") (pin "6") (pinfunction "G1_6") (pintype "input"))
      (node (ref "IC3") (pin "11") (pinfunction "ENC_11") (pintype "input"))
      (node (ref "IC4") (pin "11") (pinfunction "ENC_11") (pintype "input"))
      (node (ref "IC9") (pin "11") (pinfunction "ENC_11") (pintype "input"))
      (node (ref "R1") (pin "2") (pinfunction "2_2") (pintype "passive"))
      (node (ref "R12") (pin "2") (pinfunction "2_2") (pintype "passive"))
      (node (ref "R14") (pin "2") (pinfunction "2_2") (pintype "passive"))
      (node (ref "R2") (pin "2") (pinfunction "2_2") (pintype "passive"))
      (node (ref "R3") (pin "2") (pinfunction "2_2") (pintype "passive"))
      (node (ref "R5") (pin "2") (pinfunction "2_2") (pintype "passive"))
      (node (ref "R6") (pin "2") (pinfunction "2_2") (pintype "passive"))
      (node (ref "R7") (pin "2") (pinfunction "2_2") (pintype "passive"))
      (node (ref "R8") (pin "2") (pinfunction "2_2") (pintype "passive"))
      (node (ref "R9") (pin "2") (pinfunction "2_2") (pintype "passive"))
      (node (ref "S2") (pin "A") (pinfunction "A_A") (pintype "passive"))
      (node (ref "S2") (pin "A1") (pinfunction "A1_A1") (pintype "passive"))
    )
    (net (code "243") (name "VMA") (class "Default")
      (node (ref "IC17") (pin "5") (pinfunction "VMA_5") (pintype "output"))
      (node (ref "IC18") (pin "9") (pinfunction "I0_9") (pintype "input"))
    )
    (net (code "244") (name "unconnected-(IC17A-BA-Pad7)") (class "Default")
      (node (ref "IC17") (pin "7") (pinfunction "BA_7") (pintype "output"))
    )
    (net (code "245") (name "unconnected-(IC19A-Y0-Pad15)") (class "Default")
      (node (ref "IC19") (pin "15") (pinfunction "Y0_15") (pintype "output"))
    )
    (net (code "246") (name "unconnected-(IC19A-Y1-Pad14)") (class "Default")
      (node (ref "IC19") (pin "14") (pinfunction "Y1_14") (pintype "output"))
    )
    (net (code "247") (name "unconnected-(IC19A-Y2-Pad13)") (class "Default")
      (node (ref "IC19") (pin "13") (pinfunction "Y2_13") (pintype "output"))
    )
    (net (code "248") (name "unconnected-(IC19A-Y3-Pad12)") (class "Default")
      (node (ref "IC19") (pin "12") (pinfunction "Y3_12") (pintype "output"))
    )
    (net (code "249") (name "unconnected-(IC19A-Y4-Pad11)") (class "Default")
      (node (ref "IC19") (pin "11") (pinfunction "Y4_11") (pintype "output"))
    )
    (net (code "250") (name "unconnected-(IC19A-Y5-Pad10)") (class "Default")
      (node (ref "IC19") (pin "10") (pinfunction "Y5_10") (pintype "output"))
    )
    (net (code "251") (name "unconnected-(IC20A-R2OUT-Pad9)") (class "Default")
      (node (ref "IC20") (pin "9") (pinfunction "R2OUT_9") (pintype "output"))
    )
    (net (code "252") (name "unconnected-(IC28A-Y1-Pad14)") (class "Default")
      (node (ref "IC28") (pin "14") (pinfunction "Y1_14") (pintype "output"))
    )
    (net (code "253") (name "unconnected-(IC28A-Y2-Pad13)") (class "Default")
      (node (ref "IC28") (pin "13") (pinfunction "Y2_13") (pintype "output"))
    )
    (net (code "254") (name "unconnected-(IC28A-Y3-Pad12)") (class "Default")
      (node (ref "IC28") (pin "12") (pinfunction "Y3_12") (pintype "output"))
    )
    (net (code "255") (name "unconnected-(IC28A-Y4-Pad11)") (class "Default")
      (node (ref "IC28") (pin "11") (pinfunction "Y4_11") (pintype "output"))
    )
    (net (code "256") (name "unconnected-(R11-PadS)") (class "Default")
      (node (ref "R11") (pin "S") (pinfunction "S_S") (pintype "passive"))
    )
    (net (code "257") (name "unconnected-(SV8-Pad1)") (class "Default")
      (node (ref "SV8") (pin "1") (pinfunction "1_1") (pintype "passive"))
    )
    (net (code "258") (name "unconnected-(SV8-Pad2)") (class "Default")
      (node (ref "SV8") (pin "2") (pinfunction "2_2") (pintype "passive"))
    )
    (net (code "259") (name "unconnected-(SV8-Pad3)") (class "Default")
      (node (ref "SV8") (pin "3") (pinfunction "3_3") (pintype "passive"))
    )
    (net (code "260") (name "unconnected-(SV8-Pad4)") (class "Default")
      (node (ref "SV8") (pin "4") (pinfunction "4_4") (pintype "passive"))
    )
    (net (code "261") (name "unconnected-(SV8-Pad5)") (class "Default")
      (node (ref "SV8") (pin "5") (pinfunction "5_5") (pintype "passive"))
    )
    (net (code "262") (name "unconnected-(SV8-Pad6)") (class "Default")
      (node (ref "SV8") (pin "6") (pinfunction "6_6") (pintype "passive"))
    )
    (net (code "263") (name "unconnected-(SV8-Pad7)") (class "Default")
      (node (ref "SV8") (pin "7") (pinfunction "7_7") (pintype "passive"))
    )
    (net (code "264") (name "unconnected-(SV8-Pad8)") (class "Default")
      (node (ref "SV8") (pin "8") (pinfunction "8_8") (pintype "passive"))
    )
    (net (code "265") (name "unconnected-(SV8-Pad9)") (class "Default")
      (node (ref "SV8") (pin "9") (pinfunction "9_9") (pintype "passive"))
    )
    (net (code "266") (name "unconnected-(SV8-Pad10)") (class "Default")
      (node (ref "SV8") (pin "10") (pinfunction "10_10") (pintype "passive"))
    )
    (net (code "267") (name "unconnected-(SV8-Pad11)") (class "Default")
      (node (ref "SV8") (pin "11") (pinfunction "11_11") (pintype "passive"))
    )
    (net (code "268") (name "unconnected-(SV8-Pad12)") (class "Default")
      (node (ref "SV8") (pin "12") (pinfunction "12_12") (pintype "passive"))
    )
    (net (code "269") (name "unconnected-(SV8-Pad13)") (class "Default")
      (node (ref "SV8") (pin "13") (pinfunction "13_13") (pintype "passive"))
    )
    (net (code "270") (name "unconnected-(SV8-Pad14)") (class "Default")
      (node (ref "SV8") (pin "14") (pinfunction "14_14") (pintype "passive"))
    )
    (net (code "271") (name "unconnected-(SV8-Pad15)") (class "Default")
      (node (ref "SV8") (pin "15") (pinfunction "15_15") (pintype "passive"))
    )
    (net (code "272") (name "unconnected-(SV8-Pad16)") (class "Default")
      (node (ref "SV8") (pin "16") (pinfunction "16_16") (pintype "passive"))
    )
    (net (code "273") (name "unconnected-(SV8-Pad17)") (class "Default")
      (node (ref "SV8") (pin "17") (pinfunction "17_17") (pintype "passive"))
    )
    (net (code "274") (name "unconnected-(SV8-Pad18)") (class "Default")
      (node (ref "SV8") (pin "18") (pinfunction "18_18") (pintype "passive"))
    )
    (net (code "275") (name "unconnected-(SV8-Pad19)") (class "Default")
      (node (ref "SV8") (pin "19") (pinfunction "19_19") (pintype "passive"))
    )
    (net (code "276") (name "unconnected-(SV8-Pad20)") (class "Default")
      (node (ref "SV8") (pin "20") (pinfunction "20_20") (pintype "passive"))
    )
    (net (code "277") (name "unconnected-(X1-Pad1)") (class "Default")
      (node (ref "X1") (pin "1") (pinfunction "1_1") (pintype "passive"))
    )
    (net (code "278") (name "unconnected-(X1-Pad9)") (class "Default")
      (node (ref "X1") (pin "9") (pinfunction "9_9") (pintype "passive"))
    )
    (net (code "279") (name "~{AB}") (class "Default")
      (node (ref "IC22") (pin "20") (pinfunction "~{CE}_20") (pintype "input"))
      (node (ref "IC22") (pin "22") (pinfunction "~{OE}_22") (pintype "input"))
      (node (ref "IC28") (pin "10") (pinfunction "Y5_10") (pintype "output"))
    )
    (net (code "280") (name "~{CD}") (class "Default")
      (node (ref "IC28") (pin "9") (pinfunction "Y6_9") (pintype "output"))
    )
    (net (code "281") (name "~{EF}") (class "Default")
      (node (ref "IC23") (pin "20") (pinfunction "~{CE}_20") (pintype "input"))
      (node (ref "IC23") (pin "22") (pinfunction "~{OE}_22") (pintype "input"))
      (node (ref "IC28") (pin "7") (pinfunction "Y7_7") (pintype "output"))
    )
    (net (code "282") (name "~{HLT}") (class "Default")
      (node (ref "IC17") (pin "2") (pinfunction "HALT_2") (pintype "input"))
      (node (ref "R5") (pin "1") (pinfunction "1_1") (pintype "passive"))
    )
    (net (code "283") (name "~{IO-E}") (class "Default")
      (node (ref "IC19") (pin "9") (pinfunction "Y6_9") (pintype "output"))
      (node (ref "IC24") (pin "23") (pinfunction "CS2_23") (pintype "input"))
    )
    (net (code "284") (name "~{IO-F}") (class "Default")
      (node (ref "IC19") (pin "7") (pinfunction "Y7_7") (pintype "output"))
      (node (ref "IC21") (pin "9") (pinfunction "CS2_9") (pintype "input"))
    )
    (net (code "285") (name "~{IRQ}") (class "Default")
      (node (ref "IC17") (pin "4") (pinfunction "IRQ_4") (pintype "input"))
      (node (ref "IC24") (pin "37") (pinfunction "IRQB_37") (pintype "open_collector"))
      (node (ref "IC24") (pin "38") (pinfunction "IRQA_38") (pintype "open_collector"))
      (node (ref "R7") (pin "1") (pinfunction "1_1") (pintype "passive"))
    )
    (net (code "286") (name "~{NMI}") (class "Default")
      (node (ref "IC17") (pin "6") (pinfunction "NMI_6") (pintype "input"))
      (node (ref "IC21") (pin "7") (pinfunction "IRQ_7") (pintype "output"))
      (node (ref "R6") (pin "1") (pinfunction "1_1") (pintype "passive"))
    )
    (net (code "287") (name "~{RST}") (class "Default")
      (node (ref "IC17") (pin "40") (pinfunction "RESET_40") (pintype "input"))
      (node (ref "IC18") (pin "6") (pinfunction "O_6") (pintype "output"))
      (node (ref "IC24") (pin "34") (pinfunction "RESET_34") (pintype "input"))
    )
  )
)
